# NeoPixelClock.net
KiCad netlist of a schematic drawn in EAGLE
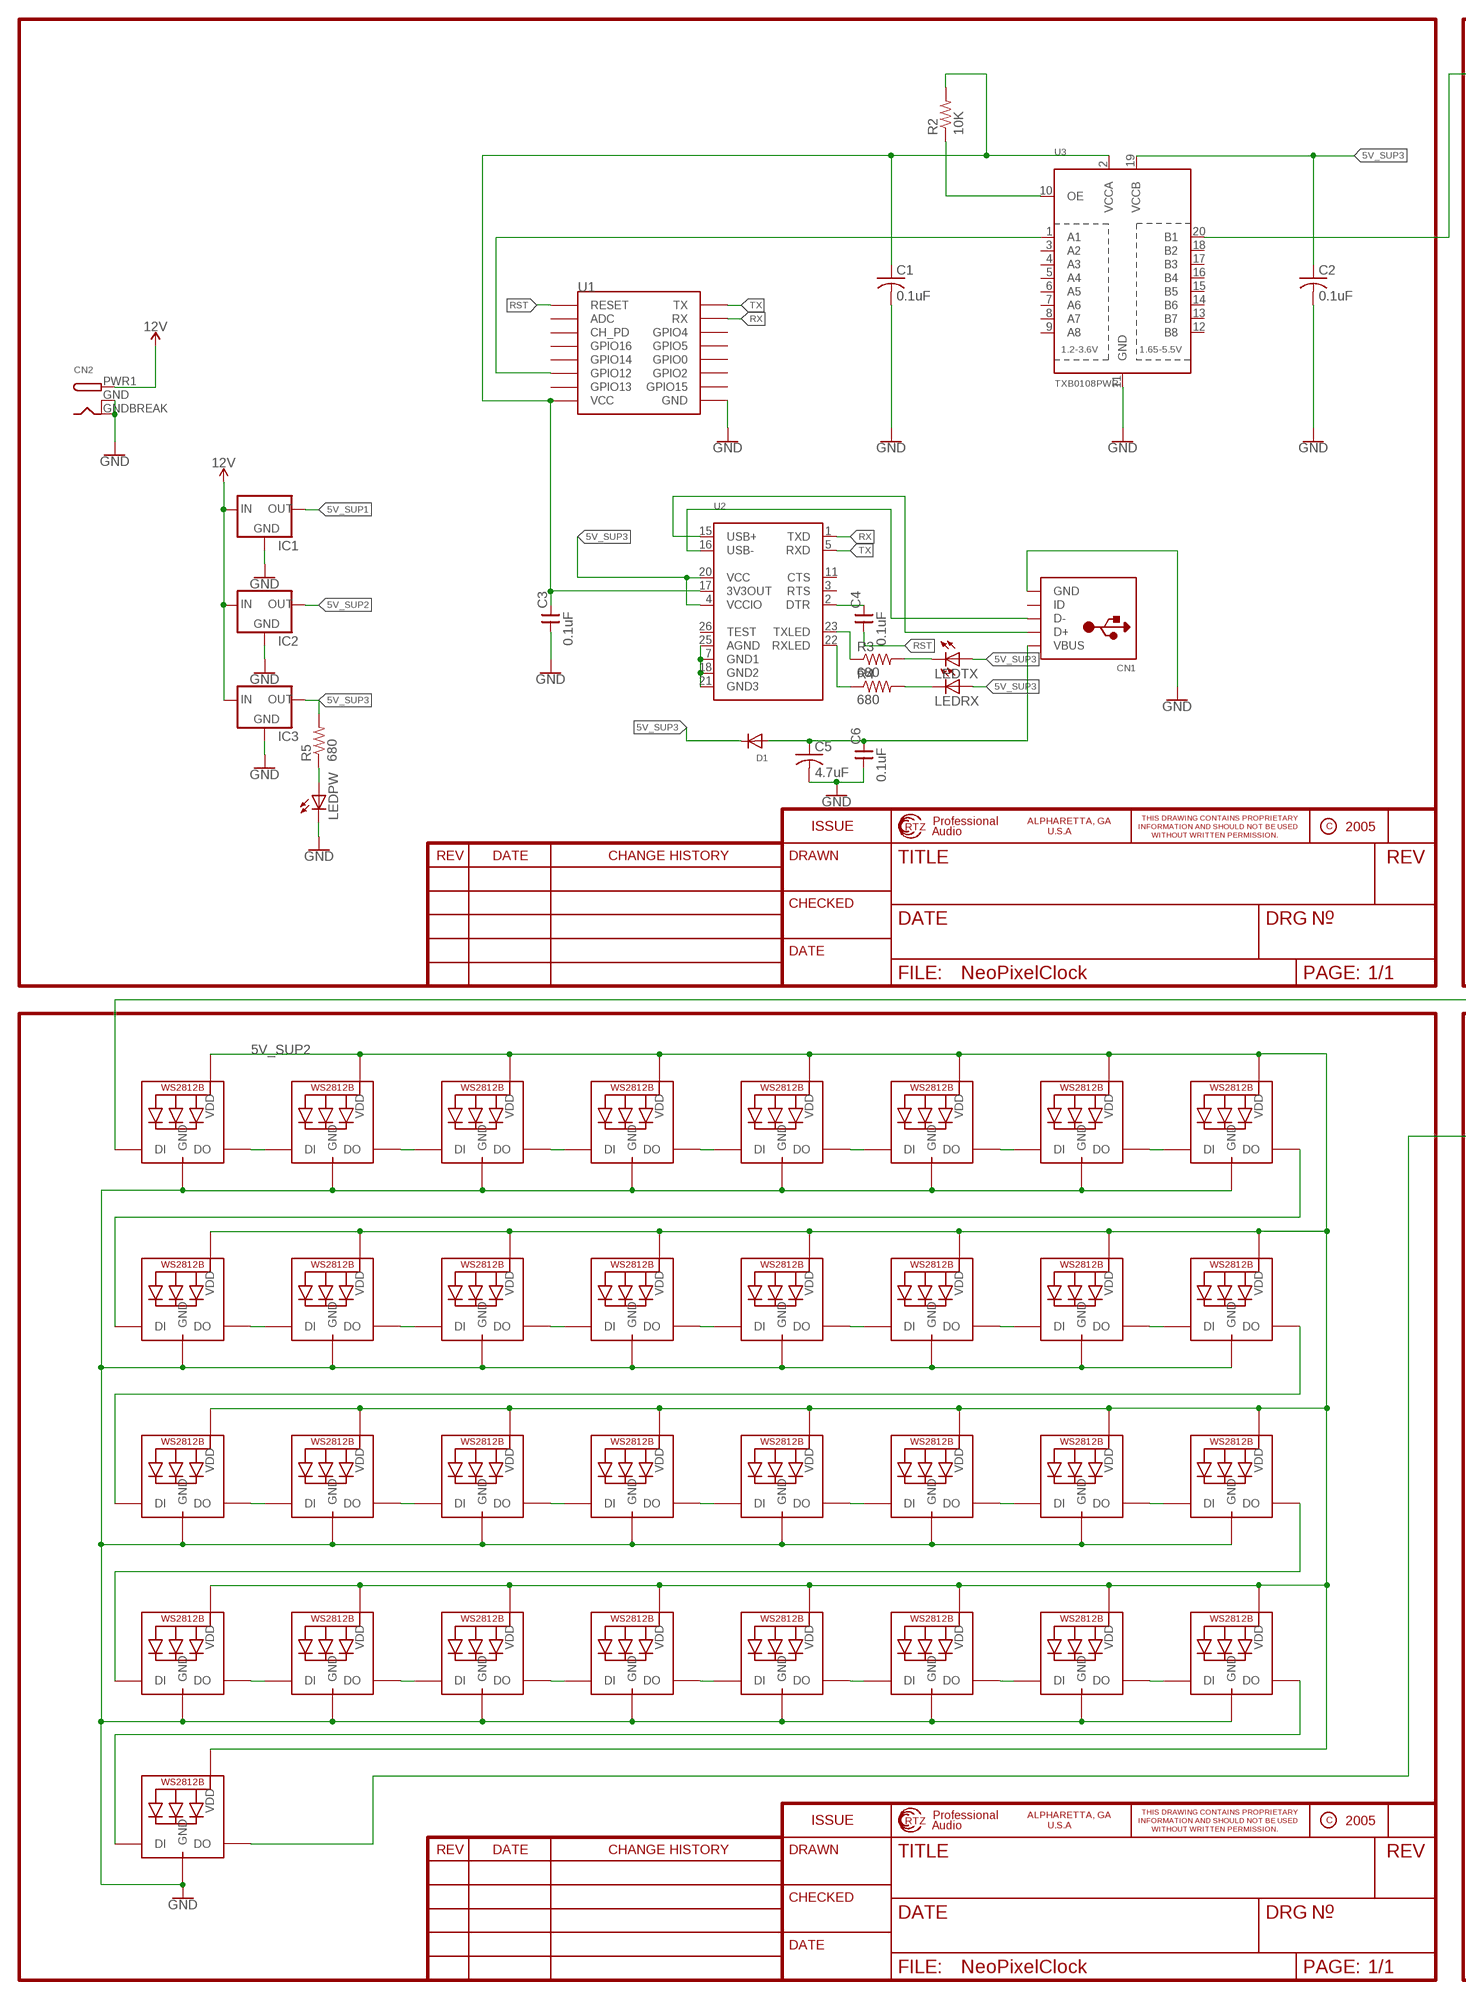
[diagram p0: schematic, sheet 1, part 1 of 2]
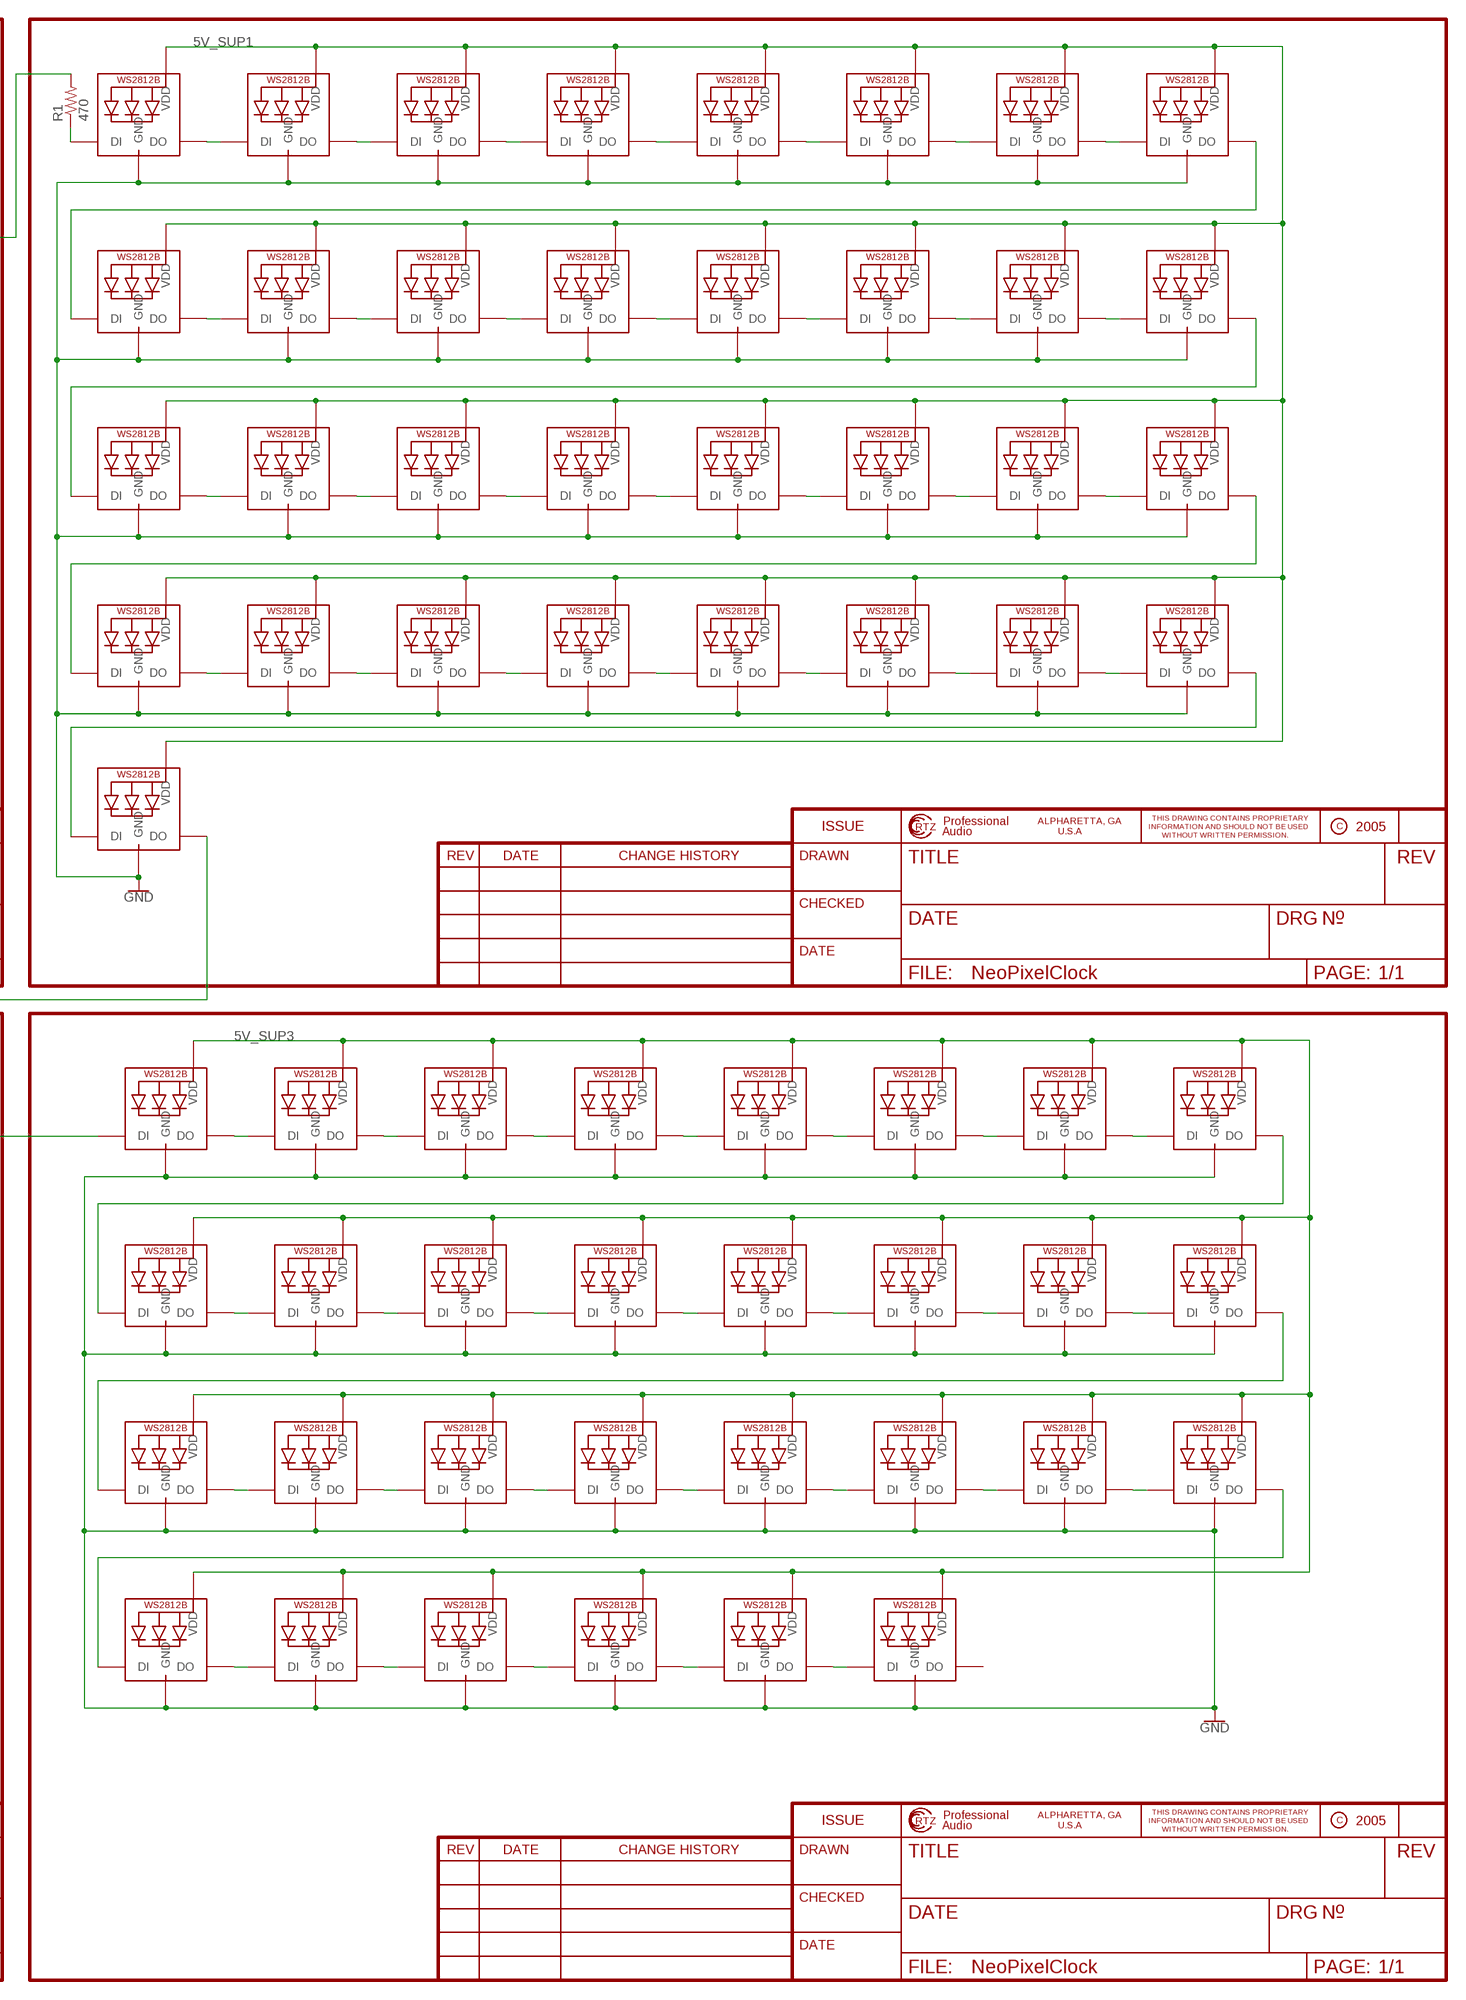
[diagram p1: schematic, sheet 1, part 2 of 2]

(export (version "E")
  (design (tool "Eeschema 10.0.6"))
  (components
    (comp (ref "C1")
      (value "0.1uF")
      (footprint "eagle-import:C0805")
      (libsource (lib "eagle-import") (part "C-USC0805"))
    )
    (comp (ref "C2")
      (value "0.1uF")
      (footprint "eagle-import:C0805")
      (libsource (lib "eagle-import") (part "C-USC0805"))
    )
    (comp (ref "C3")
      (value "0.1uF")
      (footprint "eagle-import:0805")
      (libsource (lib "eagle-import") (part "CNP-0805"))
    )
    (comp (ref "C4")
      (value "0.1uF")
      (footprint "eagle-import:0805")
      (libsource (lib "eagle-import") (part "CNP-0805"))
    )
    (comp (ref "C5")
      (value "4.7uF")
      (footprint "eagle-import:C0805")
      (libsource (lib "eagle-import") (part "C-USC0805"))
    )
    (comp (ref "C6")
      (value "0.1uF")
      (footprint "eagle-import:0805")
      (libsource (lib "eagle-import") (part "CNP-0805"))
    )
    (comp (ref "CN1")
      (value "USBMINIB")
      (footprint "eagle-import:USB-MINIB")
      (libsource (lib "eagle-import") (part "USBMINIB"))
    )
    (comp (ref "CN2")
      (value "DCBARRELSMT")
      (footprint "eagle-import:DCJACK_2MM_SMT")
      (libsource (lib "eagle-import") (part "DCBARRELSMT"))
    )
    (comp (ref "D1")
      (value "DIODESOD-123")
      (footprint "eagle-import:SOD-123")
      (libsource (lib "eagle-import") (part "DIODESOD-123"))
    )
    (comp (ref "IC1")
      (value "V_REG_78XXSIDE")
      (footprint "eagle-import:78XXL")
      (libsource (lib "eagle-import") (part "V_REG_78XXSIDE"))
    )
    (comp (ref "IC2")
      (value "V_REG_78XXSIDE")
      (footprint "eagle-import:78XXL")
      (libsource (lib "eagle-import") (part "V_REG_78XXSIDE"))
    )
    (comp (ref "IC3")
      (value "V_REG_78XXSIDE")
      (footprint "eagle-import:78XXL")
      (libsource (lib "eagle-import") (part "V_REG_78XXSIDE"))
    )
    (comp (ref "LED1")
      (value "WS2812B5050")
      (footprint "eagle-import:WS2812B")
      (libsource (lib "eagle-import") (part "WS2812B5050"))
    )
    (comp (ref "LED2")
      (value "WS2812B5050")
      (footprint "eagle-import:WS2812B")
      (libsource (lib "eagle-import") (part "WS2812B5050"))
    )
    (comp (ref "LED3")
      (value "WS2812B5050")
      (footprint "eagle-import:WS2812B")
      (libsource (lib "eagle-import") (part "WS2812B5050"))
    )
    (comp (ref "LED4")
      (value "WS2812B5050")
      (footprint "eagle-import:WS2812B")
      (libsource (lib "eagle-import") (part "WS2812B5050"))
    )
    (comp (ref "LED5")
      (value "WS2812B5050")
      (footprint "eagle-import:WS2812B")
      (libsource (lib "eagle-import") (part "WS2812B5050"))
    )
    (comp (ref "LED6")
      (value "WS2812B5050")
      (footprint "eagle-import:WS2812B")
      (libsource (lib "eagle-import") (part "WS2812B5050"))
    )
    (comp (ref "LED7")
      (value "WS2812B5050")
      (footprint "eagle-import:WS2812B")
      (libsource (lib "eagle-import") (part "WS2812B5050"))
    )
    (comp (ref "LED8")
      (value "WS2812B5050")
      (footprint "eagle-import:WS2812B")
      (libsource (lib "eagle-import") (part "WS2812B5050"))
    )
    (comp (ref "LED9")
      (value "WS2812B5050")
      (footprint "eagle-import:WS2812B")
      (libsource (lib "eagle-import") (part "WS2812B5050"))
    )
    (comp (ref "LED10")
      (value "WS2812B5050")
      (footprint "eagle-import:WS2812B")
      (libsource (lib "eagle-import") (part "WS2812B5050"))
    )
    (comp (ref "LED11")
      (value "WS2812B5050")
      (footprint "eagle-import:WS2812B")
      (libsource (lib "eagle-import") (part "WS2812B5050"))
    )
    (comp (ref "LED12")
      (value "WS2812B5050")
      (footprint "eagle-import:WS2812B")
      (libsource (lib "eagle-import") (part "WS2812B5050"))
    )
    (comp (ref "LED13")
      (value "WS2812B5050")
      (footprint "eagle-import:WS2812B")
      (libsource (lib "eagle-import") (part "WS2812B5050"))
    )
    (comp (ref "LED14")
      (value "WS2812B5050")
      (footprint "eagle-import:WS2812B")
      (libsource (lib "eagle-import") (part "WS2812B5050"))
    )
    (comp (ref "LED15")
      (value "WS2812B5050")
      (footprint "eagle-import:WS2812B")
      (libsource (lib "eagle-import") (part "WS2812B5050"))
    )
    (comp (ref "LED16")
      (value "WS2812B5050")
      (footprint "eagle-import:WS2812B")
      (libsource (lib "eagle-import") (part "WS2812B5050"))
    )
    (comp (ref "LED17")
      (value "WS2812B5050")
      (footprint "eagle-import:WS2812B")
      (libsource (lib "eagle-import") (part "WS2812B5050"))
    )
    (comp (ref "LED18")
      (value "WS2812B5050")
      (footprint "eagle-import:WS2812B")
      (libsource (lib "eagle-import") (part "WS2812B5050"))
    )
    (comp (ref "LED19")
      (value "WS2812B5050")
      (footprint "eagle-import:WS2812B")
      (libsource (lib "eagle-import") (part "WS2812B5050"))
    )
    (comp (ref "LED20")
      (value "WS2812B5050")
      (footprint "eagle-import:WS2812B")
      (libsource (lib "eagle-import") (part "WS2812B5050"))
    )
    (comp (ref "LED21")
      (value "WS2812B5050")
      (footprint "eagle-import:WS2812B")
      (libsource (lib "eagle-import") (part "WS2812B5050"))
    )
    (comp (ref "LED22")
      (value "WS2812B5050")
      (footprint "eagle-import:WS2812B")
      (libsource (lib "eagle-import") (part "WS2812B5050"))
    )
    (comp (ref "LED23")
      (value "WS2812B5050")
      (footprint "eagle-import:WS2812B")
      (libsource (lib "eagle-import") (part "WS2812B5050"))
    )
    (comp (ref "LED24")
      (value "WS2812B5050")
      (footprint "eagle-import:WS2812B")
      (libsource (lib "eagle-import") (part "WS2812B5050"))
    )
    (comp (ref "LED25")
      (value "WS2812B5050")
      (footprint "eagle-import:WS2812B")
      (libsource (lib "eagle-import") (part "WS2812B5050"))
    )
    (comp (ref "LED26")
      (value "WS2812B5050")
      (footprint "eagle-import:WS2812B")
      (libsource (lib "eagle-import") (part "WS2812B5050"))
    )
    (comp (ref "LED27")
      (value "WS2812B5050")
      (footprint "eagle-import:WS2812B")
      (libsource (lib "eagle-import") (part "WS2812B5050"))
    )
    (comp (ref "LED28")
      (value "WS2812B5050")
      (footprint "eagle-import:WS2812B")
      (libsource (lib "eagle-import") (part "WS2812B5050"))
    )
    (comp (ref "LED29")
      (value "WS2812B5050")
      (footprint "eagle-import:WS2812B")
      (libsource (lib "eagle-import") (part "WS2812B5050"))
    )
    (comp (ref "LED30")
      (value "WS2812B5050")
      (footprint "eagle-import:WS2812B")
      (libsource (lib "eagle-import") (part "WS2812B5050"))
    )
    (comp (ref "LED31")
      (value "WS2812B5050")
      (footprint "eagle-import:WS2812B")
      (libsource (lib "eagle-import") (part "WS2812B5050"))
    )
    (comp (ref "LED32")
      (value "WS2812B5050")
      (footprint "eagle-import:WS2812B")
      (libsource (lib "eagle-import") (part "WS2812B5050"))
    )
    (comp (ref "LED33")
      (value "WS2812B5050")
      (footprint "eagle-import:WS2812B")
      (libsource (lib "eagle-import") (part "WS2812B5050"))
    )
    (comp (ref "LED34")
      (value "WS2812B5050")
      (footprint "eagle-import:WS2812B")
      (libsource (lib "eagle-import") (part "WS2812B5050"))
    )
    (comp (ref "LED35")
      (value "WS2812B5050")
      (footprint "eagle-import:WS2812B")
      (libsource (lib "eagle-import") (part "WS2812B5050"))
    )
    (comp (ref "LED36")
      (value "WS2812B5050")
      (footprint "eagle-import:WS2812B")
      (libsource (lib "eagle-import") (part "WS2812B5050"))
    )
    (comp (ref "LED37")
      (value "WS2812B5050")
      (footprint "eagle-import:WS2812B")
      (libsource (lib "eagle-import") (part "WS2812B5050"))
    )
    (comp (ref "LED38")
      (value "WS2812B5050")
      (footprint "eagle-import:WS2812B")
      (libsource (lib "eagle-import") (part "WS2812B5050"))
    )
    (comp (ref "LED39")
      (value "WS2812B5050")
      (footprint "eagle-import:WS2812B")
      (libsource (lib "eagle-import") (part "WS2812B5050"))
    )
    (comp (ref "LED40")
      (value "WS2812B5050")
      (footprint "eagle-import:WS2812B")
      (libsource (lib "eagle-import") (part "WS2812B5050"))
    )
    (comp (ref "LED41")
      (value "WS2812B5050")
      (footprint "eagle-import:WS2812B")
      (libsource (lib "eagle-import") (part "WS2812B5050"))
    )
    (comp (ref "LED42")
      (value "WS2812B5050")
      (footprint "eagle-import:WS2812B")
      (libsource (lib "eagle-import") (part "WS2812B5050"))
    )
    (comp (ref "LED43")
      (value "WS2812B5050")
      (footprint "eagle-import:WS2812B")
      (libsource (lib "eagle-import") (part "WS2812B5050"))
    )
    (comp (ref "LED44")
      (value "WS2812B5050")
      (footprint "eagle-import:WS2812B")
      (libsource (lib "eagle-import") (part "WS2812B5050"))
    )
    (comp (ref "LED45")
      (value "WS2812B5050")
      (footprint "eagle-import:WS2812B")
      (libsource (lib "eagle-import") (part "WS2812B5050"))
    )
    (comp (ref "LED46")
      (value "WS2812B5050")
      (footprint "eagle-import:WS2812B")
      (libsource (lib "eagle-import") (part "WS2812B5050"))
    )
    (comp (ref "LED47")
      (value "WS2812B5050")
      (footprint "eagle-import:WS2812B")
      (libsource (lib "eagle-import") (part "WS2812B5050"))
    )
    (comp (ref "LED48")
      (value "WS2812B5050")
      (footprint "eagle-import:WS2812B")
      (libsource (lib "eagle-import") (part "WS2812B5050"))
    )
    (comp (ref "LED49")
      (value "WS2812B5050")
      (footprint "eagle-import:WS2812B")
      (libsource (lib "eagle-import") (part "WS2812B5050"))
    )
    (comp (ref "LED50")
      (value "WS2812B5050")
      (footprint "eagle-import:WS2812B")
      (libsource (lib "eagle-import") (part "WS2812B5050"))
    )
    (comp (ref "LED51")
      (value "WS2812B5050")
      (footprint "eagle-import:WS2812B")
      (libsource (lib "eagle-import") (part "WS2812B5050"))
    )
    (comp (ref "LED52")
      (value "WS2812B5050")
      (footprint "eagle-import:WS2812B")
      (libsource (lib "eagle-import") (part "WS2812B5050"))
    )
    (comp (ref "LED53")
      (value "WS2812B5050")
      (footprint "eagle-import:WS2812B")
      (libsource (lib "eagle-import") (part "WS2812B5050"))
    )
    (comp (ref "LED54")
      (value "WS2812B5050")
      (footprint "eagle-import:WS2812B")
      (libsource (lib "eagle-import") (part "WS2812B5050"))
    )
    (comp (ref "LED55")
      (value "WS2812B5050")
      (footprint "eagle-import:WS2812B")
      (libsource (lib "eagle-import") (part "WS2812B5050"))
    )
    (comp (ref "LED56")
      (value "WS2812B5050")
      (footprint "eagle-import:WS2812B")
      (libsource (lib "eagle-import") (part "WS2812B5050"))
    )
    (comp (ref "LED57")
      (value "WS2812B5050")
      (footprint "eagle-import:WS2812B")
      (libsource (lib "eagle-import") (part "WS2812B5050"))
    )
    (comp (ref "LED58")
      (value "WS2812B5050")
      (footprint "eagle-import:WS2812B")
      (libsource (lib "eagle-import") (part "WS2812B5050"))
    )
    (comp (ref "LED59")
      (value "WS2812B5050")
      (footprint "eagle-import:WS2812B")
      (libsource (lib "eagle-import") (part "WS2812B5050"))
    )
    (comp (ref "LED60")
      (value "WS2812B5050")
      (footprint "eagle-import:WS2812B")
      (libsource (lib "eagle-import") (part "WS2812B5050"))
    )
    (comp (ref "LED61")
      (value "WS2812B5050")
      (footprint "eagle-import:WS2812B")
      (libsource (lib "eagle-import") (part "WS2812B5050"))
    )
    (comp (ref "LED62")
      (value "WS2812B5050")
      (footprint "eagle-import:WS2812B")
      (libsource (lib "eagle-import") (part "WS2812B5050"))
    )
    (comp (ref "LED63")
      (value "WS2812B5050")
      (footprint "eagle-import:WS2812B")
      (libsource (lib "eagle-import") (part "WS2812B5050"))
    )
    (comp (ref "LED64")
      (value "WS2812B5050")
      (footprint "eagle-import:WS2812B")
      (libsource (lib "eagle-import") (part "WS2812B5050"))
    )
    (comp (ref "LED65")
      (value "WS2812B5050")
      (footprint "eagle-import:WS2812B")
      (libsource (lib "eagle-import") (part "WS2812B5050"))
    )
    (comp (ref "LED66")
      (value "WS2812B5050")
      (footprint "eagle-import:WS2812B")
      (libsource (lib "eagle-import") (part "WS2812B5050"))
    )
    (comp (ref "LED67")
      (value "WS2812B5050")
      (footprint "eagle-import:WS2812B")
      (libsource (lib "eagle-import") (part "WS2812B5050"))
    )
    (comp (ref "LED68")
      (value "WS2812B5050")
      (footprint "eagle-import:WS2812B")
      (libsource (lib "eagle-import") (part "WS2812B5050"))
    )
    (comp (ref "LED69")
      (value "WS2812B5050")
      (footprint "eagle-import:WS2812B")
      (libsource (lib "eagle-import") (part "WS2812B5050"))
    )
    (comp (ref "LED70")
      (value "WS2812B5050")
      (footprint "eagle-import:WS2812B")
      (libsource (lib "eagle-import") (part "WS2812B5050"))
    )
    (comp (ref "LED71")
      (value "WS2812B5050")
      (footprint "eagle-import:WS2812B")
      (libsource (lib "eagle-import") (part "WS2812B5050"))
    )
    (comp (ref "LED72")
      (value "WS2812B5050")
      (footprint "eagle-import:WS2812B")
      (libsource (lib "eagle-import") (part "WS2812B5050"))
    )
    (comp (ref "LED73")
      (value "WS2812B5050")
      (footprint "eagle-import:WS2812B")
      (libsource (lib "eagle-import") (part "WS2812B5050"))
    )
    (comp (ref "LED74")
      (value "WS2812B5050")
      (footprint "eagle-import:WS2812B")
      (libsource (lib "eagle-import") (part "WS2812B5050"))
    )
    (comp (ref "LED75")
      (value "WS2812B5050")
      (footprint "eagle-import:WS2812B")
      (libsource (lib "eagle-import") (part "WS2812B5050"))
    )
    (comp (ref "LED76")
      (value "WS2812B5050")
      (footprint "eagle-import:WS2812B")
      (libsource (lib "eagle-import") (part "WS2812B5050"))
    )
    (comp (ref "LED77")
      (value "WS2812B5050")
      (footprint "eagle-import:WS2812B")
      (libsource (lib "eagle-import") (part "WS2812B5050"))
    )
    (comp (ref "LED78")
      (value "WS2812B5050")
      (footprint "eagle-import:WS2812B")
      (libsource (lib "eagle-import") (part "WS2812B5050"))
    )
    (comp (ref "LED79")
      (value "WS2812B5050")
      (footprint "eagle-import:WS2812B")
      (libsource (lib "eagle-import") (part "WS2812B5050"))
    )
    (comp (ref "LED80")
      (value "WS2812B5050")
      (footprint "eagle-import:WS2812B")
      (libsource (lib "eagle-import") (part "WS2812B5050"))
    )
    (comp (ref "LED81")
      (value "WS2812B5050")
      (footprint "eagle-import:WS2812B")
      (libsource (lib "eagle-import") (part "WS2812B5050"))
    )
    (comp (ref "LED82")
      (value "WS2812B5050")
      (footprint "eagle-import:WS2812B")
      (libsource (lib "eagle-import") (part "WS2812B5050"))
    )
    (comp (ref "LED83")
      (value "WS2812B5050")
      (footprint "eagle-import:WS2812B")
      (libsource (lib "eagle-import") (part "WS2812B5050"))
    )
    (comp (ref "LED84")
      (value "WS2812B5050")
      (footprint "eagle-import:WS2812B")
      (libsource (lib "eagle-import") (part "WS2812B5050"))
    )
    (comp (ref "LED85")
      (value "WS2812B5050")
      (footprint "eagle-import:WS2812B")
      (libsource (lib "eagle-import") (part "WS2812B5050"))
    )
    (comp (ref "LED86")
      (value "WS2812B5050")
      (footprint "eagle-import:WS2812B")
      (libsource (lib "eagle-import") (part "WS2812B5050"))
    )
    (comp (ref "LED87")
      (value "WS2812B5050")
      (footprint "eagle-import:WS2812B")
      (libsource (lib "eagle-import") (part "WS2812B5050"))
    )
    (comp (ref "LED88")
      (value "WS2812B5050")
      (footprint "eagle-import:WS2812B")
      (libsource (lib "eagle-import") (part "WS2812B5050"))
    )
    (comp (ref "LED89")
      (value "WS2812B5050")
      (footprint "eagle-import:WS2812B")
      (libsource (lib "eagle-import") (part "WS2812B5050"))
    )
    (comp (ref "LED90")
      (value "WS2812B5050")
      (footprint "eagle-import:WS2812B")
      (libsource (lib "eagle-import") (part "WS2812B5050"))
    )
    (comp (ref "LED91")
      (value "WS2812B5050")
      (footprint "eagle-import:WS2812B")
      (libsource (lib "eagle-import") (part "WS2812B5050"))
    )
    (comp (ref "LED92")
      (value "WS2812B5050")
      (footprint "eagle-import:WS2812B")
      (libsource (lib "eagle-import") (part "WS2812B5050"))
    )
    (comp (ref "LED93")
      (value "WS2812B5050")
      (footprint "eagle-import:WS2812B")
      (libsource (lib "eagle-import") (part "WS2812B5050"))
    )
    (comp (ref "LED94")
      (value "WS2812B5050")
      (footprint "eagle-import:WS2812B")
      (libsource (lib "eagle-import") (part "WS2812B5050"))
    )
    (comp (ref "LED95")
      (value "WS2812B5050")
      (footprint "eagle-import:WS2812B")
      (libsource (lib "eagle-import") (part "WS2812B5050"))
    )
    (comp (ref "LED96")
      (value "WS2812B5050")
      (footprint "eagle-import:WS2812B")
      (libsource (lib "eagle-import") (part "WS2812B5050"))
    )
    (comp (ref "LEDPW")
      (value "LEDCHIP-LED0805")
      (footprint "eagle-import:CHIP-LED0805")
      (libsource (lib "eagle-import") (part "LEDCHIP-LED0805"))
    )
    (comp (ref "LEDRX")
      (value "LEDCHIP-LED0805")
      (footprint "eagle-import:CHIP-LED0805")
      (libsource (lib "eagle-import") (part "LEDCHIP-LED0805"))
    )
    (comp (ref "LEDTX")
      (value "LEDCHIP-LED0805")
      (footprint "eagle-import:CHIP-LED0805")
      (libsource (lib "eagle-import") (part "LEDCHIP-LED0805"))
    )
    (comp (ref "R1")
      (value "470")
      (footprint "eagle-import:M0805")
      (libsource (lib "eagle-import") (part "adafruit_420_R-US_M0805"))
    )
    (comp (ref "R2")
      (value "10K")
      (footprint "eagle-import:R0805")
      (libsource (lib "eagle-import") (part "R-US_R0805"))
    )
    (comp (ref "R3")
      (value "680")
      (footprint "eagle-import:R0805")
      (libsource (lib "eagle-import") (part "adafruit_420_R-US_R0805"))
    )
    (comp (ref "R4")
      (value "680")
      (footprint "eagle-import:R0805")
      (libsource (lib "eagle-import") (part "adafruit_420_R-US_R0805"))
    )
    (comp (ref "R5")
      (value "680")
      (footprint "eagle-import:R0805")
      (libsource (lib "eagle-import") (part "adafruit_420_R-US_R0805"))
    )
    (comp (ref "U1")
      (value "ESP12")
      (footprint "eagle-import:ESP12")
      (libsource (lib "eagle-import") (part "ESP12"))
    )
    (comp (ref "U2")
      (value "FT232RLSSOP28")
      (footprint "eagle-import:SSOP28DB")
      (libsource (lib "eagle-import") (part "FT232RLSSOP28"))
    )
    (comp (ref "U3")
      (value "TXB0108PWR")
      (footprint "eagle-import:TSSOP20")
      (libsource (lib "eagle-import") (part "TXB0108PWR"))
    )
  )
  (nets
    (net (code "1") (name "5V_SUP1") (class "Default")
      (node (ref "IC1") (pin "OUT") (pinfunction "OUT_OUT") (pintype "output"))
      (node (ref "LED1") (pin "1-VDD") (pinfunction "VDD_1-VDD") (pintype "power_in"))
      (node (ref "LED10") (pin "1-VDD") (pinfunction "VDD_1-VDD") (pintype "power_in"))
      (node (ref "LED11") (pin "1-VDD") (pinfunction "VDD_1-VDD") (pintype "power_in"))
      (node (ref "LED12") (pin "1-VDD") (pinfunction "VDD_1-VDD") (pintype "power_in"))
      (node (ref "LED13") (pin "1-VDD") (pinfunction "VDD_1-VDD") (pintype "power_in"))
      (node (ref "LED14") (pin "1-VDD") (pinfunction "VDD_1-VDD") (pintype "power_in"))
      (node (ref "LED15") (pin "1-VDD") (pinfunction "VDD_1-VDD") (pintype "power_in"))
      (node (ref "LED16") (pin "1-VDD") (pinfunction "VDD_1-VDD") (pintype "power_in"))
      (node (ref "LED17") (pin "1-VDD") (pinfunction "VDD_1-VDD") (pintype "power_in"))
      (node (ref "LED18") (pin "1-VDD") (pinfunction "VDD_1-VDD") (pintype "power_in"))
      (node (ref "LED19") (pin "1-VDD") (pinfunction "VDD_1-VDD") (pintype "power_in"))
      (node (ref "LED2") (pin "1-VDD") (pinfunction "VDD_1-VDD") (pintype "power_in"))
      (node (ref "LED20") (pin "1-VDD") (pinfunction "VDD_1-VDD") (pintype "power_in"))
      (node (ref "LED21") (pin "1-VDD") (pinfunction "VDD_1-VDD") (pintype "power_in"))
      (node (ref "LED22") (pin "1-VDD") (pinfunction "VDD_1-VDD") (pintype "power_in"))
      (node (ref "LED23") (pin "1-VDD") (pinfunction "VDD_1-VDD") (pintype "power_in"))
      (node (ref "LED24") (pin "1-VDD") (pinfunction "VDD_1-VDD") (pintype "power_in"))
      (node (ref "LED25") (pin "1-VDD") (pinfunction "VDD_1-VDD") (pintype "power_in"))
      (node (ref "LED26") (pin "1-VDD") (pinfunction "VDD_1-VDD") (pintype "power_in"))
      (node (ref "LED27") (pin "1-VDD") (pinfunction "VDD_1-VDD") (pintype "power_in"))
      (node (ref "LED28") (pin "1-VDD") (pinfunction "VDD_1-VDD") (pintype "power_in"))
      (node (ref "LED29") (pin "1-VDD") (pinfunction "VDD_1-VDD") (pintype "power_in"))
      (node (ref "LED3") (pin "1-VDD") (pinfunction "VDD_1-VDD") (pintype "power_in"))
      (node (ref "LED30") (pin "1-VDD") (pinfunction "VDD_1-VDD") (pintype "power_in"))
      (node (ref "LED31") (pin "1-VDD") (pinfunction "VDD_1-VDD") (pintype "power_in"))
      (node (ref "LED32") (pin "1-VDD") (pinfunction "VDD_1-VDD") (pintype "power_in"))
      (node (ref "LED33") (pin "1-VDD") (pinfunction "VDD_1-VDD") (pintype "power_in"))
      (node (ref "LED4") (pin "1-VDD") (pinfunction "VDD_1-VDD") (pintype "power_in"))
      (node (ref "LED5") (pin "1-VDD") (pinfunction "VDD_1-VDD") (pintype "power_in"))
      (node (ref "LED6") (pin "1-VDD") (pinfunction "VDD_1-VDD") (pintype "power_in"))
      (node (ref "LED7") (pin "1-VDD") (pinfunction "VDD_1-VDD") (pintype "power_in"))
      (node (ref "LED8") (pin "1-VDD") (pinfunction "VDD_1-VDD") (pintype "power_in"))
      (node (ref "LED9") (pin "1-VDD") (pinfunction "VDD_1-VDD") (pintype "power_in"))
    )
    (net (code "2") (name "5V_SUP2") (class "Default")
      (node (ref "IC2") (pin "OUT") (pinfunction "OUT_OUT") (pintype "output"))
      (node (ref "LED34") (pin "1-VDD") (pinfunction "VDD_1-VDD") (pintype "power_in"))
      (node (ref "LED35") (pin "1-VDD") (pinfunction "VDD_1-VDD") (pintype "power_in"))
      (node (ref "LED36") (pin "1-VDD") (pinfunction "VDD_1-VDD") (pintype "power_in"))
      (node (ref "LED37") (pin "1-VDD") (pinfunction "VDD_1-VDD") (pintype "power_in"))
      (node (ref "LED38") (pin "1-VDD") (pinfunction "VDD_1-VDD") (pintype "power_in"))
      (node (ref "LED39") (pin "1-VDD") (pinfunction "VDD_1-VDD") (pintype "power_in"))
      (node (ref "LED40") (pin "1-VDD") (pinfunction "VDD_1-VDD") (pintype "power_in"))
      (node (ref "LED41") (pin "1-VDD") (pinfunction "VDD_1-VDD") (pintype "power_in"))
      (node (ref "LED42") (pin "1-VDD") (pinfunction "VDD_1-VDD") (pintype "power_in"))
      (node (ref "LED43") (pin "1-VDD") (pinfunction "VDD_1-VDD") (pintype "power_in"))
      (node (ref "LED44") (pin "1-VDD") (pinfunction "VDD_1-VDD") (pintype "power_in"))
      (node (ref "LED45") (pin "1-VDD") (pinfunction "VDD_1-VDD") (pintype "power_in"))
      (node (ref "LED46") (pin "1-VDD") (pinfunction "VDD_1-VDD") (pintype "power_in"))
      (node (ref "LED47") (pin "1-VDD") (pinfunction "VDD_1-VDD") (pintype "power_in"))
      (node (ref "LED48") (pin "1-VDD") (pinfunction "VDD_1-VDD") (pintype "power_in"))
      (node (ref "LED49") (pin "1-VDD") (pinfunction "VDD_1-VDD") (pintype "power_in"))
      (node (ref "LED50") (pin "1-VDD") (pinfunction "VDD_1-VDD") (pintype "power_in"))
      (node (ref "LED51") (pin "1-VDD") (pinfunction "VDD_1-VDD") (pintype "power_in"))
      (node (ref "LED52") (pin "1-VDD") (pinfunction "VDD_1-VDD") (pintype "power_in"))
      (node (ref "LED53") (pin "1-VDD") (pinfunction "VDD_1-VDD") (pintype "power_in"))
      (node (ref "LED54") (pin "1-VDD") (pinfunction "VDD_1-VDD") (pintype "power_in"))
      (node (ref "LED55") (pin "1-VDD") (pinfunction "VDD_1-VDD") (pintype "power_in"))
      (node (ref "LED56") (pin "1-VDD") (pinfunction "VDD_1-VDD") (pintype "power_in"))
      (node (ref "LED57") (pin "1-VDD") (pinfunction "VDD_1-VDD") (pintype "power_in"))
      (node (ref "LED58") (pin "1-VDD") (pinfunction "VDD_1-VDD") (pintype "power_in"))
      (node (ref "LED59") (pin "1-VDD") (pinfunction "VDD_1-VDD") (pintype "power_in"))
      (node (ref "LED60") (pin "1-VDD") (pinfunction "VDD_1-VDD") (pintype "power_in"))
      (node (ref "LED61") (pin "1-VDD") (pinfunction "VDD_1-VDD") (pintype "power_in"))
      (node (ref "LED62") (pin "1-VDD") (pinfunction "VDD_1-VDD") (pintype "power_in"))
      (node (ref "LED63") (pin "1-VDD") (pinfunction "VDD_1-VDD") (pintype "power_in"))
      (node (ref "LED64") (pin "1-VDD") (pinfunction "VDD_1-VDD") (pintype "power_in"))
      (node (ref "LED65") (pin "1-VDD") (pinfunction "VDD_1-VDD") (pintype "power_in"))
      (node (ref "LED66") (pin "1-VDD") (pinfunction "VDD_1-VDD") (pintype "power_in"))
    )
    (net (code "3") (name "5V_SUP3") (class "Default")
      (node (ref "C2") (pin "1") (pinfunction "1_1") (pintype "passive"))
      (node (ref "D1") (pin "C") (pinfunction "C_C") (pintype "passive"))
      (node (ref "IC3") (pin "OUT") (pinfunction "OUT_OUT") (pintype "output"))
      (node (ref "LED67") (pin "1-VDD") (pinfunction "VDD_1-VDD") (pintype "power_in"))
      (node (ref "LED68") (pin "1-VDD") (pinfunction "VDD_1-VDD") (pintype "power_in"))
      (node (ref "LED69") (pin "1-VDD") (pinfunction "VDD_1-VDD") (pintype "power_in"))
      (node (ref "LED70") (pin "1-VDD") (pinfunction "VDD_1-VDD") (pintype "power_in"))
      (node (ref "LED71") (pin "1-VDD") (pinfunction "VDD_1-VDD") (pintype "power_in"))
      (node (ref "LED72") (pin "1-VDD") (pinfunction "VDD_1-VDD") (pintype "power_in"))
      (node (ref "LED73") (pin "1-VDD") (pinfunction "VDD_1-VDD") (pintype "power_in"))
      (node (ref "LED74") (pin "1-VDD") (pinfunction "VDD_1-VDD") (pintype "power_in"))
      (node (ref "LED75") (pin "1-VDD") (pinfunction "VDD_1-VDD") (pintype "power_in"))
      (node (ref "LED76") (pin "1-VDD") (pinfunction "VDD_1-VDD") (pintype "power_in"))
      (node (ref "LED77") (pin "1-VDD") (pinfunction "VDD_1-VDD") (pintype "power_in"))
      (node (ref "LED78") (pin "1-VDD") (pinfunction "VDD_1-VDD") (pintype "power_in"))
      (node (ref "LED79") (pin "1-VDD") (pinfunction "VDD_1-VDD") (pintype "power_in"))
      (node (ref "LED80") (pin "1-VDD") (pinfunction "VDD_1-VDD") (pintype "power_in"))
      (node (ref "LED81") (pin "1-VDD") (pinfunction "VDD_1-VDD") (pintype "power_in"))
      (node (ref "LED82") (pin "1-VDD") (pinfunction "VDD_1-VDD") (pintype "power_in"))
      (node (ref "LED83") (pin "1-VDD") (pinfunction "VDD_1-VDD") (pintype "power_in"))
      (node (ref "LED84") (pin "1-VDD") (pinfunction "VDD_1-VDD") (pintype "power_in"))
      (node (ref "LED85") (pin "1-VDD") (pinfunction "VDD_1-VDD") (pintype "power_in"))
      (node (ref "LED86") (pin "1-VDD") (pinfunction "VDD_1-VDD") (pintype "power_in"))
      (node (ref "LED87") (pin "1-VDD") (pinfunction "VDD_1-VDD") (pintype "power_in"))
      (node (ref "LED88") (pin "1-VDD") (pinfunction "VDD_1-VDD") (pintype "power_in"))
      (node (ref "LED89") (pin "1-VDD") (pinfunction "VDD_1-VDD") (pintype "power_in"))
      (node (ref "LED90") (pin "1-VDD") (pinfunction "VDD_1-VDD") (pintype "power_in"))
      (node (ref "LED91") (pin "1-VDD") (pinfunction "VDD_1-VDD") (pintype "power_in"))
      (node (ref "LED92") (pin "1-VDD") (pinfunction "VDD_1-VDD") (pintype "power_in"))
      (node (ref "LED93") (pin "1-VDD") (pinfunction "VDD_1-VDD") (pintype "power_in"))
      (node (ref "LED94") (pin "1-VDD") (pinfunction "VDD_1-VDD") (pintype "power_in"))
      (node (ref "LED95") (pin "1-VDD") (pinfunction "VDD_1-VDD") (pintype "power_in"))
      (node (ref "LED96") (pin "1-VDD") (pinfunction "VDD_1-VDD") (pintype "power_in"))
      (node (ref "LEDRX") (pin "A") (pinfunction "A_A") (pintype "passive"))
      (node (ref "LEDTX") (pin "A") (pinfunction "A_A") (pintype "passive"))
      (node (ref "R5") (pin "2") (pinfunction "2_2") (pintype "passive"))
      (node (ref "U2") (pin "20") (pinfunction "VCC_20") (pintype "power_in"))
      (node (ref "U2") (pin "4") (pinfunction "VCCIO_4") (pintype "power_in"))
      (node (ref "U3") (pin "19") (pinfunction "VCCB_19") (pintype "bidirectional"))
    )
    (net (code "4") (name "12V") (class "Default")
      (node (ref "CN2") (pin "PWR1") (pinfunction "PWR_PWR1") (pintype "power_in"))
      (node (ref "IC1") (pin "IN") (pinfunction "IN_IN") (pintype "input"))
      (node (ref "IC2") (pin "IN") (pinfunction "IN_IN") (pintype "input"))
      (node (ref "IC3") (pin "IN") (pinfunction "IN_IN") (pintype "input"))
    )
    (net (code "5") (name "GND") (class "Default")
      (node (ref "C1") (pin "2") (pinfunction "2_2") (pintype "passive"))
      (node (ref "C2") (pin "2") (pinfunction "2_2") (pintype "passive"))
      (node (ref "C3") (pin "1") (pinfunction "1_1") (pintype "passive"))
      (node (ref "C5") (pin "2") (pinfunction "2_2") (pintype "passive"))
      (node (ref "C6") (pin "1") (pinfunction "1_1") (pintype "passive"))
      (node (ref "CN1") (pin "GND") (pinfunction "GND_GND") (pintype "power_in"))
      (node (ref "CN2") (pin "GND") (pinfunction "GNDBREAK_GND") (pintype "power_in"))
      (node (ref "CN2") (pin "GNDBREAK") (pinfunction "GND_GNDBREAK") (pintype "power_in"))
      (node (ref "IC1") (pin "GND") (pinfunction "GND_GND") (pintype "input"))
      (node (ref "IC2") (pin "GND") (pinfunction "GND_GND") (pintype "input"))
      (node (ref "IC3") (pin "GND") (pinfunction "GND_GND") (pintype "input"))
      (node (ref "LED1") (pin "3-GND") (pinfunction "GND_3-GND") (pintype "power_in"))
      (node (ref "LED10") (pin "3-GND") (pinfunction "GND_3-GND") (pintype "power_in"))
      (node (ref "LED11") (pin "3-GND") (pinfunction "GND_3-GND") (pintype "power_in"))
      (node (ref "LED12") (pin "3-GND") (pinfunction "GND_3-GND") (pintype "power_in"))
      (node (ref "LED13") (pin "3-GND") (pinfunction "GND_3-GND") (pintype "power_in"))
      (node (ref "LED14") (pin "3-GND") (pinfunction "GND_3-GND") (pintype "power_in"))
      (node (ref "LED15") (pin "3-GND") (pinfunction "GND_3-GND") (pintype "power_in"))
      (node (ref "LED16") (pin "3-GND") (pinfunction "GND_3-GND") (pintype "power_in"))
      (node (ref "LED17") (pin "3-GND") (pinfunction "GND_3-GND") (pintype "power_in"))
      (node (ref "LED18") (pin "3-GND") (pinfunction "GND_3-GND") (pintype "power_in"))
      (node (ref "LED19") (pin "3-GND") (pinfunction "GND_3-GND") (pintype "power_in"))
      (node (ref "LED2") (pin "3-GND") (pinfunction "GND_3-GND") (pintype "power_in"))
      (node (ref "LED20") (pin "3-GND") (pinfunction "GND_3-GND") (pintype "power_in"))
      (node (ref "LED21") (pin "3-GND") (pinfunction "GND_3-GND") (pintype "power_in"))
      (node (ref "LED22") (pin "3-GND") (pinfunction "GND_3-GND") (pintype "power_in"))
      (node (ref "LED23") (pin "3-GND") (pinfunction "GND_3-GND") (pintype "power_in"))
      (node (ref "LED24") (pin "3-GND") (pinfunction "GND_3-GND") (pintype "power_in"))
      (node (ref "LED25") (pin "3-GND") (pinfunction "GND_3-GND") (pintype "power_in"))
      (node (ref "LED26") (pin "3-GND") (pinfunction "GND_3-GND") (pintype "power_in"))
      (node (ref "LED27") (pin "3-GND") (pinfunction "GND_3-GND") (pintype "power_in"))
      (node (ref "LED28") (pin "3-GND") (pinfunction "GND_3-GND") (pintype "power_in"))
      (node (ref "LED29") (pin "3-GND") (pinfunction "GND_3-GND") (pintype "power_in"))
      (node (ref "LED3") (pin "3-GND") (pinfunction "GND_3-GND") (pintype "power_in"))
      (node (ref "LED30") (pin "3-GND") (pinfunction "GND_3-GND") (pintype "power_in"))
      (node (ref "LED31") (pin "3-GND") (pinfunction "GND_3-GND") (pintype "power_in"))
      (node (ref "LED32") (pin "3-GND") (pinfunction "GND_3-GND") (pintype "power_in"))
      (node (ref "LED33") (pin "3-GND") (pinfunction "GND_3-GND") (pintype "power_in"))
      (node (ref "LED34") (pin "3-GND") (pinfunction "GND_3-GND") (pintype "power_in"))
      (node (ref "LED35") (pin "3-GND") (pinfunction "GND_3-GND") (pintype "power_in"))
      (node (ref "LED36") (pin "3-GND") (pinfunction "GND_3-GND") (pintype "power_in"))
      (node (ref "LED37") (pin "3-GND") (pinfunction "GND_3-GND") (pintype "power_in"))
      (node (ref "LED38") (pin "3-GND") (pinfunction "GND_3-GND") (pintype "power_in"))
      (node (ref "LED39") (pin "3-GND") (pinfunction "GND_3-GND") (pintype "power_in"))
      (node (ref "LED4") (pin "3-GND") (pinfunction "GND_3-GND") (pintype "power_in"))
      (node (ref "LED40") (pin "3-GND") (pinfunction "GND_3-GND") (pintype "power_in"))
      (node (ref "LED41") (pin "3-GND") (pinfunction "GND_3-GND") (pintype "power_in"))
      (node (ref "LED42") (pin "3-GND") (pinfunction "GND_3-GND") (pintype "power_in"))
      (node (ref "LED43") (pin "3-GND") (pinfunction "GND_3-GND") (pintype "power_in"))
      (node (ref "LED44") (pin "3-GND") (pinfunction "GND_3-GND") (pintype "power_in"))
      (node (ref "LED45") (pin "3-GND") (pinfunction "GND_3-GND") (pintype "power_in"))
      (node (ref "LED46") (pin "3-GND") (pinfunction "GND_3-GND") (pintype "power_in"))
      (node (ref "LED47") (pin "3-GND") (pinfunction "GND_3-GND") (pintype "power_in"))
      (node (ref "LED48") (pin "3-GND") (pinfunction "GND_3-GND") (pintype "power_in"))
      (node (ref "LED49") (pin "3-GND") (pinfunction "GND_3-GND") (pintype "power_in"))
      (node (ref "LED5") (pin "3-GND") (pinfunction "GND_3-GND") (pintype "power_in"))
      (node (ref "LED50") (pin "3-GND") (pinfunction "GND_3-GND") (pintype "power_in"))
      (node (ref "LED51") (pin "3-GND") (pinfunction "GND_3-GND") (pintype "power_in"))
      (node (ref "LED52") (pin "3-GND") (pinfunction "GND_3-GND") (pintype "power_in"))
      (node (ref "LED53") (pin "3-GND") (pinfunction "GND_3-GND") (pintype "power_in"))
      (node (ref "LED54") (pin "3-GND") (pinfunction "GND_3-GND") (pintype "power_in"))
      (node (ref "LED55") (pin "3-GND") (pinfunction "GND_3-GND") (pintype "power_in"))
      (node (ref "LED56") (pin "3-GND") (pinfunction "GND_3-GND") (pintype "power_in"))
      (node (ref "LED57") (pin "3-GND") (pinfunction "GND_3-GND") (pintype "power_in"))
      (node (ref "LED58") (pin "3-GND") (pinfunction "GND_3-GND") (pintype "power_in"))
      (node (ref "LED59") (pin "3-GND") (pinfunction "GND_3-GND") (pintype "power_in"))
      (node (ref "LED6") (pin "3-GND") (pinfunction "GND_3-GND") (pintype "power_in"))
      (node (ref "LED60") (pin "3-GND") (pinfunction "GND_3-GND") (pintype "power_in"))
      (node (ref "LED61") (pin "3-GND") (pinfunction "GND_3-GND") (pintype "power_in"))
      (node (ref "LED62") (pin "3-GND") (pinfunction "GND_3-GND") (pintype "power_in"))
      (node (ref "LED63") (pin "3-GND") (pinfunction "GND_3-GND") (pintype "power_in"))
      (node (ref "LED64") (pin "3-GND") (pinfunction "GND_3-GND") (pintype "power_in"))
      (node (ref "LED65") (pin "3-GND") (pinfunction "GND_3-GND") (pintype "power_in"))
      (node (ref "LED66") (pin "3-GND") (pinfunction "GND_3-GND") (pintype "power_in"))
      (node (ref "LED67") (pin "3-GND") (pinfunction "GND_3-GND") (pintype "power_in"))
      (node (ref "LED68") (pin "3-GND") (pinfunction "GND_3-GND") (pintype "power_in"))
      (node (ref "LED69") (pin "3-GND") (pinfunction "GND_3-GND") (pintype "power_in"))
      (node (ref "LED7") (pin "3-GND") (pinfunction "GND_3-GND") (pintype "power_in"))
      (node (ref "LED70") (pin "3-GND") (pinfunction "GND_3-GND") (pintype "power_in"))
      (node (ref "LED71") (pin "3-GND") (pinfunction "GND_3-GND") (pintype "power_in"))
      (node (ref "LED72") (pin "3-GND") (pinfunction "GND_3-GND") (pintype "power_in"))
      (node (ref "LED73") (pin "3-GND") (pinfunction "GND_3-GND") (pintype "power_in"))
      (node (ref "LED74") (pin "3-GND") (pinfunction "GND_3-GND") (pintype "power_in"))
      (node (ref "LED75") (pin "3-GND") (pinfunction "GND_3-GND") (pintype "power_in"))
      (node (ref "LED76") (pin "3-GND") (pinfunction "GND_3-GND") (pintype "power_in"))
      (node (ref "LED77") (pin "3-GND") (pinfunction "GND_3-GND") (pintype "power_in"))
      (node (ref "LED78") (pin "3-GND") (pinfunction "GND_3-GND") (pintype "power_in"))
      (node (ref "LED79") (pin "3-GND") (pinfunction "GND_3-GND") (pintype "power_in"))
      (node (ref "LED8") (pin "3-GND") (pinfunction "GND_3-GND") (pintype "power_in"))
      (node (ref "LED80") (pin "3-GND") (pinfunction "GND_3-GND") (pintype "power_in"))
      (node (ref "LED81") (pin "3-GND") (pinfunction "GND_3-GND") (pintype "power_in"))
      (node (ref "LED82") (pin "3-GND") (pinfunction "GND_3-GND") (pintype "power_in"))
      (node (ref "LED83") (pin "3-GND") (pinfunction "GND_3-GND") (pintype "power_in"))
      (node (ref "LED84") (pin "3-GND") (pinfunction "GND_3-GND") (pintype "power_in"))
      (node (ref "LED85") (pin "3-GND") (pinfunction "GND_3-GND") (pintype "power_in"))
      (node (ref "LED86") (pin "3-GND") (pinfunction "GND_3-GND") (pintype "power_in"))
      (node (ref "LED87") (pin "3-GND") (pinfunction "GND_3-GND") (pintype "power_in"))
      (node (ref "LED88") (pin "3-GND") (pinfunction "GND_3-GND") (pintype "power_in"))
      (node (ref "LED89") (pin "3-GND") (pinfunction "GND_3-GND") (pintype "power_in"))
      (node (ref "LED9") (pin "3-GND") (pinfunction "GND_3-GND") (pintype "power_in"))
      (node (ref "LED90") (pin "3-GND") (pinfunction "GND_3-GND") (pintype "power_in"))
      (node (ref "LED91") (pin "3-GND") (pinfunction "GND_3-GND") (pintype "power_in"))
      (node (ref "LED92") (pin "3-GND") (pinfunction "GND_3-GND") (pintype "power_in"))
      (node (ref "LED93") (pin "3-GND") (pinfunction "GND_3-GND") (pintype "power_in"))
      (node (ref "LED94") (pin "3-GND") (pinfunction "GND_3-GND") (pintype "power_in"))
      (node (ref "LED95") (pin "3-GND") (pinfunction "GND_3-GND") (pintype "power_in"))
      (node (ref "LED96") (pin "3-GND") (pinfunction "GND_3-GND") (pintype "power_in"))
      (node (ref "LEDPW") (pin "C") (pinfunction "C_C") (pintype "passive"))
      (node (ref "U1") (pin "GND") (pinfunction "GND_GND") (pintype "bidirectional"))
      (node (ref "U3") (pin "11") (pinfunction "GND_11") (pintype "bidirectional"))
    )
    (net (code "6") (name "Net-(C5-Pad1)") (class "Default")
      (node (ref "C5") (pin "1") (pinfunction "1_1") (pintype "passive"))
      (node (ref "C6") (pin "2") (pinfunction "2_2") (pintype "passive"))
      (node (ref "CN1") (pin "VBUS") (pinfunction "VBUS_VBUS") (pintype "power_in"))
      (node (ref "D1") (pin "A") (pinfunction "A_A") (pintype "passive"))
    )
    (net (code "7") (name "Net-(LED1-DI)") (class "Default")
      (node (ref "LED1") (pin "4-DIN") (pinfunction "DI_4-DIN") (pintype "input"))
      (node (ref "R1") (pin "1") (pinfunction "1_1") (pintype "passive"))
    )
    (net (code "8") (name "Net-(LED1-DO)") (class "Default")
      (node (ref "LED1") (pin "2-DOUT") (pinfunction "DO_2-DOUT") (pintype "output"))
      (node (ref "LED2") (pin "4-DIN") (pinfunction "DI_4-DIN") (pintype "input"))
    )
    (net (code "9") (name "Net-(LED2-DO)") (class "Default")
      (node (ref "LED2") (pin "2-DOUT") (pinfunction "DO_2-DOUT") (pintype "output"))
      (node (ref "LED3") (pin "4-DIN") (pinfunction "DI_4-DIN") (pintype "input"))
    )
    (net (code "10") (name "Net-(LED3-DO)") (class "Default")
      (node (ref "LED3") (pin "2-DOUT") (pinfunction "DO_2-DOUT") (pintype "output"))
      (node (ref "LED4") (pin "4-DIN") (pinfunction "DI_4-DIN") (pintype "input"))
    )
    (net (code "11") (name "Net-(LED4-DO)") (class "Default")
      (node (ref "LED4") (pin "2-DOUT") (pinfunction "DO_2-DOUT") (pintype "output"))
      (node (ref "LED5") (pin "4-DIN") (pinfunction "DI_4-DIN") (pintype "input"))
    )
    (net (code "12") (name "Net-(LED5-DO)") (class "Default")
      (node (ref "LED5") (pin "2-DOUT") (pinfunction "DO_2-DOUT") (pintype "output"))
      (node (ref "LED6") (pin "4-DIN") (pinfunction "DI_4-DIN") (pintype "input"))
    )
    (net (code "13") (name "Net-(LED6-DO)") (class "Default")
      (node (ref "LED6") (pin "2-DOUT") (pinfunction "DO_2-DOUT") (pintype "output"))
      (node (ref "LED7") (pin "4-DIN") (pinfunction "DI_4-DIN") (pintype "input"))
    )
    (net (code "14") (name "Net-(LED7-DO)") (class "Default")
      (node (ref "LED7") (pin "2-DOUT") (pinfunction "DO_2-DOUT") (pintype "output"))
      (node (ref "LED8") (pin "4-DIN") (pinfunction "DI_4-DIN") (pintype "input"))
    )
    (net (code "15") (name "Net-(LED8-DO)") (class "Default")
      (node (ref "LED8") (pin "2-DOUT") (pinfunction "DO_2-DOUT") (pintype "output"))
      (node (ref "LED9") (pin "4-DIN") (pinfunction "DI_4-DIN") (pintype "input"))
    )
    (net (code "16") (name "Net-(LED10-DI)") (class "Default")
      (node (ref "LED10") (pin "4-DIN") (pinfunction "DI_4-DIN") (pintype "input"))
      (node (ref "LED9") (pin "2-DOUT") (pinfunction "DO_2-DOUT") (pintype "output"))
    )
    (net (code "17") (name "Net-(LED10-DO)") (class "Default")
      (node (ref "LED10") (pin "2-DOUT") (pinfunction "DO_2-DOUT") (pintype "output"))
      (node (ref "LED11") (pin "4-DIN") (pinfunction "DI_4-DIN") (pintype "input"))
    )
    (net (code "18") (name "Net-(LED11-DO)") (class "Default")
      (node (ref "LED11") (pin "2-DOUT") (pinfunction "DO_2-DOUT") (pintype "output"))
      (node (ref "LED12") (pin "4-DIN") (pinfunction "DI_4-DIN") (pintype "input"))
    )
    (net (code "19") (name "Net-(LED12-DO)") (class "Default")
      (node (ref "LED12") (pin "2-DOUT") (pinfunction "DO_2-DOUT") (pintype "output"))
      (node (ref "LED13") (pin "4-DIN") (pinfunction "DI_4-DIN") (pintype "input"))
    )
    (net (code "20") (name "Net-(LED13-DO)") (class "Default")
      (node (ref "LED13") (pin "2-DOUT") (pinfunction "DO_2-DOUT") (pintype "output"))
      (node (ref "LED14") (pin "4-DIN") (pinfunction "DI_4-DIN") (pintype "input"))
    )
    (net (code "21") (name "Net-(LED14-DO)") (class "Default")
      (node (ref "LED14") (pin "2-DOUT") (pinfunction "DO_2-DOUT") (pintype "output"))
      (node (ref "LED15") (pin "4-DIN") (pinfunction "DI_4-DIN") (pintype "input"))
    )
    (net (code "22") (name "Net-(LED15-DO)") (class "Default")
      (node (ref "LED15") (pin "2-DOUT") (pinfunction "DO_2-DOUT") (pintype "output"))
      (node (ref "LED16") (pin "4-DIN") (pinfunction "DI_4-DIN") (pintype "input"))
    )
    (net (code "23") (name "Net-(LED16-DO)") (class "Default")
      (node (ref "LED16") (pin "2-DOUT") (pinfunction "DO_2-DOUT") (pintype "output"))
      (node (ref "LED17") (pin "4-DIN") (pinfunction "DI_4-DIN") (pintype "input"))
    )
    (net (code "24") (name "Net-(LED17-DO)") (class "Default")
      (node (ref "LED17") (pin "2-DOUT") (pinfunction "DO_2-DOUT") (pintype "output"))
      (node (ref "LED18") (pin "4-DIN") (pinfunction "DI_4-DIN") (pintype "input"))
    )
    (net (code "25") (name "Net-(LED18-DO)") (class "Default")
      (node (ref "LED18") (pin "2-DOUT") (pinfunction "DO_2-DOUT") (pintype "output"))
      (node (ref "LED19") (pin "4-DIN") (pinfunction "DI_4-DIN") (pintype "input"))
    )
    (net (code "26") (name "Net-(LED19-DO)") (class "Default")
      (node (ref "LED19") (pin "2-DOUT") (pinfunction "DO_2-DOUT") (pintype "output"))
      (node (ref "LED20") (pin "4-DIN") (pinfunction "DI_4-DIN") (pintype "input"))
    )
    (net (code "27") (name "Net-(LED20-DO)") (class "Default")
      (node (ref "LED20") (pin "2-DOUT") (pinfunction "DO_2-DOUT") (pintype "output"))
      (node (ref "LED21") (pin "4-DIN") (pinfunction "DI_4-DIN") (pintype "input"))
    )
    (net (code "28") (name "Net-(LED21-DO)") (class "Default")
      (node (ref "LED21") (pin "2-DOUT") (pinfunction "DO_2-DOUT") (pintype "output"))
      (node (ref "LED22") (pin "4-DIN") (pinfunction "DI_4-DIN") (pintype "input"))
    )
    (net (code "29") (name "Net-(LED22-DO)") (class "Default")
      (node (ref "LED22") (pin "2-DOUT") (pinfunction "DO_2-DOUT") (pintype "output"))
      (node (ref "LED23") (pin "4-DIN") (pinfunction "DI_4-DIN") (pintype "input"))
    )
    (net (code "30") (name "Net-(LED23-DO)") (class "Default")
      (node (ref "LED23") (pin "2-DOUT") (pinfunction "DO_2-DOUT") (pintype "output"))
      (node (ref "LED24") (pin "4-DIN") (pinfunction "DI_4-DIN") (pintype "input"))
    )
    (net (code "31") (name "Net-(LED24-DO)") (class "Default")
      (node (ref "LED24") (pin "2-DOUT") (pinfunction "DO_2-DOUT") (pintype "output"))
      (node (ref "LED25") (pin "4-DIN") (pinfunction "DI_4-DIN") (pintype "input"))
    )
    (net (code "32") (name "Net-(LED25-DO)") (class "Default")
      (node (ref "LED25") (pin "2-DOUT") (pinfunction "DO_2-DOUT") (pintype "output"))
      (node (ref "LED26") (pin "4-DIN") (pinfunction "DI_4-DIN") (pintype "input"))
    )
    (net (code "33") (name "Net-(LED26-DO)") (class "Default")
      (node (ref "LED26") (pin "2-DOUT") (pinfunction "DO_2-DOUT") (pintype "output"))
      (node (ref "LED27") (pin "4-DIN") (pinfunction "DI_4-DIN") (pintype "input"))
    )
    (net (code "34") (name "Net-(LED27-DO)") (class "Default")
      (node (ref "LED27") (pin "2-DOUT") (pinfunction "DO_2-DOUT") (pintype "output"))
      (node (ref "LED28") (pin "4-DIN") (pinfunction "DI_4-DIN") (pintype "input"))
    )
    (net (code "35") (name "Net-(LED28-DO)") (class "Default")
      (node (ref "LED28") (pin "2-DOUT") (pinfunction "DO_2-DOUT") (pintype "output"))
      (node (ref "LED29") (pin "4-DIN") (pinfunction "DI_4-DIN") (pintype "input"))
    )
    (net (code "36") (name "Net-(LED29-DO)") (class "Default")
      (node (ref "LED29") (pin "2-DOUT") (pinfunction "DO_2-DOUT") (pintype "output"))
      (node (ref "LED30") (pin "4-DIN") (pinfunction "DI_4-DIN") (pintype "input"))
    )
    (net (code "37") (name "Net-(LED30-DO)") (class "Default")
      (node (ref "LED30") (pin "2-DOUT") (pinfunction "DO_2-DOUT") (pintype "output"))
      (node (ref "LED31") (pin "4-DIN") (pinfunction "DI_4-DIN") (pintype "input"))
    )
    (net (code "38") (name "Net-(LED31-DO)") (class "Default")
      (node (ref "LED31") (pin "2-DOUT") (pinfunction "DO_2-DOUT") (pintype "output"))
      (node (ref "LED32") (pin "4-DIN") (pinfunction "DI_4-DIN") (pintype "input"))
    )
    (net (code "39") (name "Net-(LED32-DO)") (class "Default")
      (node (ref "LED32") (pin "2-DOUT") (pinfunction "DO_2-DOUT") (pintype "output"))
      (node (ref "LED33") (pin "4-DIN") (pinfunction "DI_4-DIN") (pintype "input"))
    )
    (net (code "40") (name "Net-(LED33-DO)") (class "Default")
      (node (ref "LED33") (pin "2-DOUT") (pinfunction "DO_2-DOUT") (pintype "output"))
      (node (ref "LED34") (pin "4-DIN") (pinfunction "DI_4-DIN") (pintype "input"))
    )
    (net (code "41") (name "Net-(LED34-DO)") (class "Default")
      (node (ref "LED34") (pin "2-DOUT") (pinfunction "DO_2-DOUT") (pintype "output"))
      (node (ref "LED35") (pin "4-DIN") (pinfunction "DI_4-DIN") (pintype "input"))
    )
    (net (code "42") (name "Net-(LED35-DO)") (class "Default")
      (node (ref "LED35") (pin "2-DOUT") (pinfunction "DO_2-DOUT") (pintype "output"))
      (node (ref "LED36") (pin "4-DIN") (pinfunction "DI_4-DIN") (pintype "input"))
    )
    (net (code "43") (name "Net-(LED36-DO)") (class "Default")
      (node (ref "LED36") (pin "2-DOUT") (pinfunction "DO_2-DOUT") (pintype "output"))
      (node (ref "LED37") (pin "4-DIN") (pinfunction "DI_4-DIN") (pintype "input"))
    )
    (net (code "44") (name "Net-(LED37-DO)") (class "Default")
      (node (ref "LED37") (pin "2-DOUT") (pinfunction "DO_2-DOUT") (pintype "output"))
      (node (ref "LED38") (pin "4-DIN") (pinfunction "DI_4-DIN") (pintype "input"))
    )
    (net (code "45") (name "Net-(LED38-DO)") (class "Default")
      (node (ref "LED38") (pin "2-DOUT") (pinfunction "DO_2-DOUT") (pintype "output"))
      (node (ref "LED39") (pin "4-DIN") (pinfunction "DI_4-DIN") (pintype "input"))
    )
    (net (code "46") (name "Net-(LED39-DO)") (class "Default")
      (node (ref "LED39") (pin "2-DOUT") (pinfunction "DO_2-DOUT") (pintype "output"))
      (node (ref "LED40") (pin "4-DIN") (pinfunction "DI_4-DIN") (pintype "input"))
    )
    (net (code "47") (name "Net-(LED40-DO)") (class "Default")
      (node (ref "LED40") (pin "2-DOUT") (pinfunction "DO_2-DOUT") (pintype "output"))
      (node (ref "LED41") (pin "4-DIN") (pinfunction "DI_4-DIN") (pintype "input"))
    )
    (net (code "48") (name "Net-(LED41-DO)") (class "Default")
      (node (ref "LED41") (pin "2-DOUT") (pinfunction "DO_2-DOUT") (pintype "output"))
      (node (ref "LED42") (pin "4-DIN") (pinfunction "DI_4-DIN") (pintype "input"))
    )
    (net (code "49") (name "Net-(LED42-DO)") (class "Default")
      (node (ref "LED42") (pin "2-DOUT") (pinfunction "DO_2-DOUT") (pintype "output"))
      (node (ref "LED43") (pin "4-DIN") (pinfunction "DI_4-DIN") (pintype "input"))
    )
    (net (code "50") (name "Net-(LED43-DO)") (class "Default")
      (node (ref "LED43") (pin "2-DOUT") (pinfunction "DO_2-DOUT") (pintype "output"))
      (node (ref "LED44") (pin "4-DIN") (pinfunction "DI_4-DIN") (pintype "input"))
    )
    (net (code "51") (name "Net-(LED44-DO)") (class "Default")
      (node (ref "LED44") (pin "2-DOUT") (pinfunction "DO_2-DOUT") (pintype "output"))
      (node (ref "LED45") (pin "4-DIN") (pinfunction "DI_4-DIN") (pintype "input"))
    )
    (net (code "52") (name "Net-(LED45-DO)") (class "Default")
      (node (ref "LED45") (pin "2-DOUT") (pinfunction "DO_2-DOUT") (pintype "output"))
      (node (ref "LED46") (pin "4-DIN") (pinfunction "DI_4-DIN") (pintype "input"))
    )
    (net (code "53") (name "Net-(LED46-DO)") (class "Default")
      (node (ref "LED46") (pin "2-DOUT") (pinfunction "DO_2-DOUT") (pintype "output"))
      (node (ref "LED47") (pin "4-DIN") (pinfunction "DI_4-DIN") (pintype "input"))
    )
    (net (code "54") (name "Net-(LED47-DO)") (class "Default")
      (node (ref "LED47") (pin "2-DOUT") (pinfunction "DO_2-DOUT") (pintype "output"))
      (node (ref "LED48") (pin "4-DIN") (pinfunction "DI_4-DIN") (pintype "input"))
    )
    (net (code "55") (name "Net-(LED48-DO)") (class "Default")
      (node (ref "LED48") (pin "2-DOUT") (pinfunction "DO_2-DOUT") (pintype "output"))
      (node (ref "LED49") (pin "4-DIN") (pinfunction "DI_4-DIN") (pintype "input"))
    )
    (net (code "56") (name "Net-(LED49-DO)") (class "Default")
      (node (ref "LED49") (pin "2-DOUT") (pinfunction "DO_2-DOUT") (pintype "output"))
      (node (ref "LED50") (pin "4-DIN") (pinfunction "DI_4-DIN") (pintype "input"))
    )
    (net (code "57") (name "Net-(LED50-DO)") (class "Default")
      (node (ref "LED50") (pin "2-DOUT") (pinfunction "DO_2-DOUT") (pintype "output"))
      (node (ref "LED51") (pin "4-DIN") (pinfunction "DI_4-DIN") (pintype "input"))
    )
    (net (code "58") (name "Net-(LED51-DO)") (class "Default")
      (node (ref "LED51") (pin "2-DOUT") (pinfunction "DO_2-DOUT") (pintype "output"))
      (node (ref "LED52") (pin "4-DIN") (pinfunction "DI_4-DIN") (pintype "input"))
    )
    (net (code "59") (name "Net-(LED52-DO)") (class "Default")
      (node (ref "LED52") (pin "2-DOUT") (pinfunction "DO_2-DOUT") (pintype "output"))
      (node (ref "LED53") (pin "4-DIN") (pinfunction "DI_4-DIN") (pintype "input"))
    )
    (net (code "60") (name "Net-(LED53-DO)") (class "Default")
      (node (ref "LED53") (pin "2-DOUT") (pinfunction "DO_2-DOUT") (pintype "output"))
      (node (ref "LED54") (pin "4-DIN") (pinfunction "DI_4-DIN") (pintype "input"))
    )
    (net (code "61") (name "Net-(LED54-DO)") (class "Default")
      (node (ref "LED54") (pin "2-DOUT") (pinfunction "DO_2-DOUT") (pintype "output"))
      (node (ref "LED55") (pin "4-DIN") (pinfunction "DI_4-DIN") (pintype "input"))
    )
    (net (code "62") (name "Net-(LED55-DO)") (class "Default")
      (node (ref "LED55") (pin "2-DOUT") (pinfunction "DO_2-DOUT") (pintype "output"))
      (node (ref "LED56") (pin "4-DIN") (pinfunction "DI_4-DIN") (pintype "input"))
    )
    (net (code "63") (name "Net-(LED56-DO)") (class "Default")
      (node (ref "LED56") (pin "2-DOUT") (pinfunction "DO_2-DOUT") (pintype "output"))
      (node (ref "LED57") (pin "4-DIN") (pinfunction "DI_4-DIN") (pintype "input"))
    )
    (net (code "64") (name "Net-(LED57-DO)") (class "Default")
      (node (ref "LED57") (pin "2-DOUT") (pinfunction "DO_2-DOUT") (pintype "output"))
      (node (ref "LED58") (pin "4-DIN") (pinfunction "DI_4-DIN") (pintype "input"))
    )
    (net (code "65") (name "Net-(LED58-DO)") (class "Default")
      (node (ref "LED58") (pin "2-DOUT") (pinfunction "DO_2-DOUT") (pintype "output"))
      (node (ref "LED59") (pin "4-DIN") (pinfunction "DI_4-DIN") (pintype "input"))
    )
    (net (code "66") (name "Net-(LED59-DO)") (class "Default")
      (node (ref "LED59") (pin "2-DOUT") (pinfunction "DO_2-DOUT") (pintype "output"))
      (node (ref "LED60") (pin "4-DIN") (pinfunction "DI_4-DIN") (pintype "input"))
    )
    (net (code "67") (name "Net-(LED60-DO)") (class "Default")
      (node (ref "LED60") (pin "2-DOUT") (pinfunction "DO_2-DOUT") (pintype "output"))
      (node (ref "LED61") (pin "4-DIN") (pinfunction "DI_4-DIN") (pintype "input"))
    )
    (net (code "68") (name "Net-(LED61-DO)") (class "Default")
      (node (ref "LED61") (pin "2-DOUT") (pinfunction "DO_2-DOUT") (pintype "output"))
      (node (ref "LED62") (pin "4-DIN") (pinfunction "DI_4-DIN") (pintype "input"))
    )
    (net (code "69") (name "Net-(LED62-DO)") (class "Default")
      (node (ref "LED62") (pin "2-DOUT") (pinfunction "DO_2-DOUT") (pintype "output"))
      (node (ref "LED63") (pin "4-DIN") (pinfunction "DI_4-DIN") (pintype "input"))
    )
    (net (code "70") (name "Net-(LED63-DO)") (class "Default")
      (node (ref "LED63") (pin "2-DOUT") (pinfunction "DO_2-DOUT") (pintype "output"))
      (node (ref "LED64") (pin "4-DIN") (pinfunction "DI_4-DIN") (pintype "input"))
    )
    (net (code "71") (name "Net-(LED64-DO)") (class "Default")
      (node (ref "LED64") (pin "2-DOUT") (pinfunction "DO_2-DOUT") (pintype "output"))
      (node (ref "LED65") (pin "4-DIN") (pinfunction "DI_4-DIN") (pintype "input"))
    )
    (net (code "72") (name "Net-(LED65-DO)") (class "Default")
      (node (ref "LED65") (pin "2-DOUT") (pinfunction "DO_2-DOUT") (pintype "output"))
      (node (ref "LED66") (pin "4-DIN") (pinfunction "DI_4-DIN") (pintype "input"))
    )
    (net (code "73") (name "Net-(LED66-DO)") (class "Default")
      (node (ref "LED66") (pin "2-DOUT") (pinfunction "DO_2-DOUT") (pintype "output"))
      (node (ref "LED67") (pin "4-DIN") (pinfunction "DI_4-DIN") (pintype "input"))
    )
    (net (code "74") (name "Net-(LED67-DO)") (class "Default")
      (node (ref "LED67") (pin "2-DOUT") (pinfunction "DO_2-DOUT") (pintype "output"))
      (node (ref "LED68") (pin "4-DIN") (pinfunction "DI_4-DIN") (pintype "input"))
    )
    (net (code "75") (name "Net-(LED68-DO)") (class "Default")
      (node (ref "LED68") (pin "2-DOUT") (pinfunction "DO_2-DOUT") (pintype "output"))
      (node (ref "LED69") (pin "4-DIN") (pinfunction "DI_4-DIN") (pintype "input"))
    )
    (net (code "76") (name "Net-(LED69-DO)") (class "Default")
      (node (ref "LED69") (pin "2-DOUT") (pinfunction "DO_2-DOUT") (pintype "output"))
      (node (ref "LED70") (pin "4-DIN") (pinfunction "DI_4-DIN") (pintype "input"))
    )
    (net (code "77") (name "Net-(LED70-DO)") (class "Default")
      (node (ref "LED70") (pin "2-DOUT") (pinfunction "DO_2-DOUT") (pintype "output"))
      (node (ref "LED71") (pin "4-DIN") (pinfunction "DI_4-DIN") (pintype "input"))
    )
    (net (code "78") (name "Net-(LED71-DO)") (class "Default")
      (node (ref "LED71") (pin "2-DOUT") (pinfunction "DO_2-DOUT") (pintype "output"))
      (node (ref "LED72") (pin "4-DIN") (pinfunction "DI_4-DIN") (pintype "input"))
    )
    (net (code "79") (name "Net-(LED72-DO)") (class "Default")
      (node (ref "LED72") (pin "2-DOUT") (pinfunction "DO_2-DOUT") (pintype "output"))
      (node (ref "LED73") (pin "4-DIN") (pinfunction "DI_4-DIN") (pintype "input"))
    )
    (net (code "80") (name "Net-(LED73-DO)") (class "Default")
      (node (ref "LED73") (pin "2-DOUT") (pinfunction "DO_2-DOUT") (pintype "output"))
      (node (ref "LED74") (pin "4-DIN") (pinfunction "DI_4-DIN") (pintype "input"))
    )
    (net (code "81") (name "Net-(LED74-DO)") (class "Default")
      (node (ref "LED74") (pin "2-DOUT") (pinfunction "DO_2-DOUT") (pintype "output"))
      (node (ref "LED75") (pin "4-DIN") (pinfunction "DI_4-DIN") (pintype "input"))
    )
    (net (code "82") (name "Net-(LED75-DO)") (class "Default")
      (node (ref "LED75") (pin "2-DOUT") (pinfunction "DO_2-DOUT") (pintype "output"))
      (node (ref "LED76") (pin "4-DIN") (pinfunction "DI_4-DIN") (pintype "input"))
    )
    (net (code "83") (name "Net-(LED76-DO)") (class "Default")
      (node (ref "LED76") (pin "2-DOUT") (pinfunction "DO_2-DOUT") (pintype "output"))
      (node (ref "LED77") (pin "4-DIN") (pinfunction "DI_4-DIN") (pintype "input"))
    )
    (net (code "84") (name "Net-(LED77-DO)") (class "Default")
      (node (ref "LED77") (pin "2-DOUT") (pinfunction "DO_2-DOUT") (pintype "output"))
      (node (ref "LED78") (pin "4-DIN") (pinfunction "DI_4-DIN") (pintype "input"))
    )
    (net (code "85") (name "Net-(LED78-DO)") (class "Default")
      (node (ref "LED78") (pin "2-DOUT") (pinfunction "DO_2-DOUT") (pintype "output"))
      (node (ref "LED79") (pin "4-DIN") (pinfunction "DI_4-DIN") (pintype "input"))
    )
    (net (code "86") (name "Net-(LED79-DO)") (class "Default")
      (node (ref "LED79") (pin "2-DOUT") (pinfunction "DO_2-DOUT") (pintype "output"))
      (node (ref "LED80") (pin "4-DIN") (pinfunction "DI_4-DIN") (pintype "input"))
    )
    (net (code "87") (name "Net-(LED80-DO)") (class "Default")
      (node (ref "LED80") (pin "2-DOUT") (pinfunction "DO_2-DOUT") (pintype "output"))
      (node (ref "LED81") (pin "4-DIN") (pinfunction "DI_4-DIN") (pintype "input"))
    )
    (net (code "88") (name "Net-(LED81-DO)") (class "Default")
      (node (ref "LED81") (pin "2-DOUT") (pinfunction "DO_2-DOUT") (pintype "output"))
      (node (ref "LED82") (pin "4-DIN") (pinfunction "DI_4-DIN") (pintype "input"))
    )
    (net (code "89") (name "Net-(LED82-DO)") (class "Default")
      (node (ref "LED82") (pin "2-DOUT") (pinfunction "DO_2-DOUT") (pintype "output"))
      (node (ref "LED83") (pin "4-DIN") (pinfunction "DI_4-DIN") (pintype "input"))
    )
    (net (code "90") (name "Net-(LED83-DO)") (class "Default")
      (node (ref "LED83") (pin "2-DOUT") (pinfunction "DO_2-DOUT") (pintype "output"))
      (node (ref "LED84") (pin "4-DIN") (pinfunction "DI_4-DIN") (pintype "input"))
    )
    (net (code "91") (name "Net-(LED84-DO)") (class "Default")
      (node (ref "LED84") (pin "2-DOUT") (pinfunction "DO_2-DOUT") (pintype "output"))
      (node (ref "LED85") (pin "4-DIN") (pinfunction "DI_4-DIN") (pintype "input"))
    )
    (net (code "92") (name "Net-(LED85-DO)") (class "Default")
      (node (ref "LED85") (pin "2-DOUT") (pinfunction "DO_2-DOUT") (pintype "output"))
      (node (ref "LED86") (pin "4-DIN") (pinfunction "DI_4-DIN") (pintype "input"))
    )
    (net (code "93") (name "Net-(LED86-DO)") (class "Default")
      (node (ref "LED86") (pin "2-DOUT") (pinfunction "DO_2-DOUT") (pintype "output"))
      (node (ref "LED87") (pin "4-DIN") (pinfunction "DI_4-DIN") (pintype "input"))
    )
    (net (code "94") (name "Net-(LED87-DO)") (class "Default")
      (node (ref "LED87") (pin "2-DOUT") (pinfunction "DO_2-DOUT") (pintype "output"))
      (node (ref "LED88") (pin "4-DIN") (pinfunction "DI_4-DIN") (pintype "input"))
    )
    (net (code "95") (name "Net-(LED88-DO)") (class "Default")
      (node (ref "LED88") (pin "2-DOUT") (pinfunction "DO_2-DOUT") (pintype "output"))
      (node (ref "LED89") (pin "4-DIN") (pinfunction "DI_4-DIN") (pintype "input"))
    )
    (net (code "96") (name "Net-(LED89-DO)") (class "Default")
      (node (ref "LED89") (pin "2-DOUT") (pinfunction "DO_2-DOUT") (pintype "output"))
      (node (ref "LED90") (pin "4-DIN") (pinfunction "DI_4-DIN") (pintype "input"))
    )
    (net (code "97") (name "Net-(LED90-DO)") (class "Default")
      (node (ref "LED90") (pin "2-DOUT") (pinfunction "DO_2-DOUT") (pintype "output"))
      (node (ref "LED91") (pin "4-DIN") (pinfunction "DI_4-DIN") (pintype "input"))
    )
    (net (code "98") (name "Net-(LED91-DO)") (class "Default")
      (node (ref "LED91") (pin "2-DOUT") (pinfunction "DO_2-DOUT") (pintype "output"))
      (node (ref "LED92") (pin "4-DIN") (pinfunction "DI_4-DIN") (pintype "input"))
    )
    (net (code "99") (name "Net-(LED92-DO)") (class "Default")
      (node (ref "LED92") (pin "2-DOUT") (pinfunction "DO_2-DOUT") (pintype "output"))
      (node (ref "LED93") (pin "4-DIN") (pinfunction "DI_4-DIN") (pintype "input"))
    )
    (net (code "100") (name "Net-(LED93-DO)") (class "Default")
      (node (ref "LED93") (pin "2-DOUT") (pinfunction "DO_2-DOUT") (pintype "output"))
      (node (ref "LED94") (pin "4-DIN") (pinfunction "DI_4-DIN") (pintype "input"))
    )
    (net (code "101") (name "Net-(LED94-DO)") (class "Default")
      (node (ref "LED94") (pin "2-DOUT") (pinfunction "DO_2-DOUT") (pintype "output"))
      (node (ref "LED95") (pin "4-DIN") (pinfunction "DI_4-DIN") (pintype "input"))
    )
    (net (code "102") (name "Net-(LED95-DO)") (class "Default")
      (node (ref "LED95") (pin "2-DOUT") (pinfunction "DO_2-DOUT") (pintype "output"))
      (node (ref "LED96") (pin "4-DIN") (pinfunction "DI_4-DIN") (pintype "input"))
    )
    (net (code "103") (name "Net-(LEDPW-PadA)") (class "Default")
      (node (ref "LEDPW") (pin "A") (pinfunction "A_A") (pintype "passive"))
      (node (ref "R5") (pin "1") (pinfunction "1_1") (pintype "passive"))
    )
    (net (code "104") (name "Net-(LEDRX-PadC)") (class "Default")
      (node (ref "LEDRX") (pin "C") (pinfunction "C_C") (pintype "passive"))
      (node (ref "R4") (pin "2") (pinfunction "2_2") (pintype "passive"))
    )
    (net (code "105") (name "Net-(LEDTX-PadC)") (class "Default")
      (node (ref "LEDTX") (pin "C") (pinfunction "C_C") (pintype "passive"))
      (node (ref "R3") (pin "2") (pinfunction "2_2") (pintype "passive"))
    )
    (net (code "106") (name "Net-(U2-3V3OUT)") (class "Default")
      (node (ref "C1") (pin "1") (pinfunction "1_1") (pintype "passive"))
      (node (ref "C3") (pin "2") (pinfunction "2_2") (pintype "passive"))
      (node (ref "R2") (pin "2") (pinfunction "2_2") (pintype "passive"))
      (node (ref "U1") (pin "VCC") (pinfunction "VCC_VCC") (pintype "bidirectional"))
      (node (ref "U2") (pin "17") (pinfunction "3V3OUT_17") (pintype "power_in"))
      (node (ref "U3") (pin "2") (pinfunction "VCCA_2") (pintype "bidirectional"))
    )
    (net (code "107") (name "Net-(U2-AGND)") (class "Default")
      (node (ref "U2") (pin "18") (pinfunction "GND2_18") (pintype "power_in"))
      (node (ref "U2") (pin "21") (pinfunction "GND3_21") (pintype "power_in"))
      (node (ref "U2") (pin "25") (pinfunction "AGND_25") (pintype "power_in"))
      (node (ref "U2") (pin "7") (pinfunction "GND1_7") (pintype "power_in"))
    )
    (net (code "108") (name "Net-(U2-DTR)") (class "Default")
      (node (ref "C4") (pin "2") (pinfunction "2_2") (pintype "passive"))
      (node (ref "U2") (pin "2") (pinfunction "DTR_2") (pintype "bidirectional"))
    )
    (net (code "109") (name "Net-(U2-RXLED)") (class "Default")
      (node (ref "R4") (pin "1") (pinfunction "1_1") (pintype "passive"))
      (node (ref "U2") (pin "22") (pinfunction "RXLED_22") (pintype "bidirectional"))
    )
    (net (code "110") (name "Net-(U2-TXLED)") (class "Default")
      (node (ref "R3") (pin "1") (pinfunction "1_1") (pintype "passive"))
      (node (ref "U2") (pin "23") (pinfunction "TXLED_23") (pintype "bidirectional"))
    )
    (net (code "111") (name "Net-(U2-USB+)") (class "Default")
      (node (ref "CN1") (pin "D+") (pinfunction "D+_D+") (pintype "bidirectional"))
      (node (ref "U2") (pin "15") (pinfunction "USB+_15") (pintype "bidirectional"))
    )
    (net (code "112") (name "Net-(U2-USB-)") (class "Default")
      (node (ref "CN1") (pin "D-") (pinfunction "D-_D-") (pintype "bidirectional"))
      (node (ref "U2") (pin "16") (pinfunction "USB-_16") (pintype "bidirectional"))
    )
    (net (code "113") (name "Net-(U3-A1)") (class "Default")
      (node (ref "U1") (pin "GPIO12") (pinfunction "GPIO12_GPIO12") (pintype "bidirectional"))
      (node (ref "U3") (pin "1") (pinfunction "A1_1") (pintype "bidirectional"))
    )
    (net (code "114") (name "Net-(U3-B1)") (class "Default")
      (node (ref "R1") (pin "2") (pinfunction "2_2") (pintype "passive"))
      (node (ref "U3") (pin "20") (pinfunction "B1_20") (pintype "bidirectional"))
    )
    (net (code "115") (name "Net-(U3-OE)") (class "Default")
      (node (ref "R2") (pin "1") (pinfunction "1_1") (pintype "passive"))
      (node (ref "U3") (pin "10") (pinfunction "OE_10") (pintype "bidirectional"))
    )
    (net (code "116") (name "RST") (class "Default")
      (node (ref "C4") (pin "1") (pinfunction "1_1") (pintype "passive"))
      (node (ref "U1") (pin "RESET") (pinfunction "RESET_RESET") (pintype "bidirectional"))
    )
    (net (code "117") (name "RX") (class "Default")
      (node (ref "U1") (pin "RX") (pinfunction "RX_RX") (pintype "bidirectional"))
      (node (ref "U2") (pin "1") (pinfunction "TXD_1") (pintype "output"))
    )
    (net (code "118") (name "TX") (class "Default")
      (node (ref "U1") (pin "TX") (pinfunction "TX_TX") (pintype "bidirectional"))
      (node (ref "U2") (pin "5") (pinfunction "RXD_5") (pintype "input"))
    )
    (net (code "119") (name "unconnected-(CN1-PadID)") (class "Default")
      (node (ref "CN1") (pin "ID") (pinfunction "ID_ID") (pintype "bidirectional"))
    )
    (net (code "120") (name "unconnected-(LED96-DO-Pad2-DOUT)") (class "Default")
      (node (ref "LED96") (pin "2-DOUT") (pinfunction "DO_2-DOUT") (pintype "output"))
    )
    (net (code "121") (name "unconnected-(U1-PadADC)") (class "Default")
      (node (ref "U1") (pin "ADC") (pinfunction "ADC_ADC") (pintype "bidirectional"))
    )
    (net (code "122") (name "unconnected-(U1-PadCH_PD)") (class "Default")
      (node (ref "U1") (pin "CH_PD") (pinfunction "CH_PD_CH_PD") (pintype "bidirectional"))
    )
    (net (code "123") (name "unconnected-(U1-PadGPIO0)") (class "Default")
      (node (ref "U1") (pin "GPIO0") (pinfunction "GPIO0_GPIO0") (pintype "bidirectional"))
    )
    (net (code "124") (name "unconnected-(U1-PadGPIO2)") (class "Default")
      (node (ref "U1") (pin "GPIO2") (pinfunction "GPIO2_GPIO2") (pintype "bidirectional"))
    )
    (net (code "125") (name "unconnected-(U1-PadGPIO4)") (class "Default")
      (node (ref "U1") (pin "GPIO4") (pinfunction "GPIO4_GPIO4") (pintype "bidirectional"))
    )
    (net (code "126") (name "unconnected-(U1-PadGPIO5)") (class "Default")
      (node (ref "U1") (pin "GPIO5") (pinfunction "GPIO5_GPIO5") (pintype "bidirectional"))
    )
    (net (code "127") (name "unconnected-(U1-PadGPIO13)") (class "Default")
      (node (ref "U1") (pin "GPIO13") (pinfunction "GPIO13_GPIO13") (pintype "bidirectional"))
    )
    (net (code "128") (name "unconnected-(U1-PadGPIO14)") (class "Default")
      (node (ref "U1") (pin "GPIO14") (pinfunction "GPIO14_GPIO14") (pintype "bidirectional"))
    )
    (net (code "129") (name "unconnected-(U1-PadGPIO15)") (class "Default")
      (node (ref "U1") (pin "GPIO15") (pinfunction "GPIO15_GPIO15") (pintype "bidirectional"))
    )
    (net (code "130") (name "unconnected-(U1-PadGPIO16)") (class "Default")
      (node (ref "U1") (pin "GPIO16") (pinfunction "GPIO16_GPIO16") (pintype "bidirectional"))
    )
    (net (code "131") (name "unconnected-(U2-CTS-Pad11)") (class "Default")
      (node (ref "U2") (pin "11") (pinfunction "CTS_11") (pintype "bidirectional"))
    )
    (net (code "132") (name "unconnected-(U2-RTS-Pad3)") (class "Default")
      (node (ref "U2") (pin "3") (pinfunction "RTS_3") (pintype "bidirectional"))
    )
    (net (code "133") (name "unconnected-(U2-TEST-Pad26)") (class "Default")
      (node (ref "U2") (pin "26") (pinfunction "TEST_26") (pintype "input"))
    )
    (net (code "134") (name "unconnected-(U3-A2-Pad3)") (class "Default")
      (node (ref "U3") (pin "3") (pinfunction "A2_3") (pintype "bidirectional"))
    )
    (net (code "135") (name "unconnected-(U3-A3-Pad4)") (class "Default")
      (node (ref "U3") (pin "4") (pinfunction "A3_4") (pintype "bidirectional"))
    )
    (net (code "136") (name "unconnected-(U3-A4-Pad5)") (class "Default")
      (node (ref "U3") (pin "5") (pinfunction "A4_5") (pintype "bidirectional"))
    )
    (net (code "137") (name "unconnected-(U3-A5-Pad6)") (class "Default")
      (node (ref "U3") (pin "6") (pinfunction "A5_6") (pintype "bidirectional"))
    )
    (net (code "138") (name "unconnected-(U3-A6-Pad7)") (class "Default")
      (node (ref "U3") (pin "7") (pinfunction "A6_7") (pintype "bidirectional"))
    )
    (net (code "139") (name "unconnected-(U3-A7-Pad8)") (class "Default")
      (node (ref "U3") (pin "8") (pinfunction "A7_8") (pintype "bidirectional"))
    )
    (net (code "140") (name "unconnected-(U3-A8-Pad9)") (class "Default")
      (node (ref "U3") (pin "9") (pinfunction "A8_9") (pintype "bidirectional"))
    )
    (net (code "141") (name "unconnected-(U3-B2-Pad18)") (class "Default")
      (node (ref "U3") (pin "18") (pinfunction "B2_18") (pintype "bidirectional"))
    )
    (net (code "142") (name "unconnected-(U3-B3-Pad17)") (class "Default")
      (node (ref "U3") (pin "17") (pinfunction "B3_17") (pintype "bidirectional"))
    )
    (net (code "143") (name "unconnected-(U3-B4-Pad16)") (class "Default")
      (node (ref "U3") (pin "16") (pinfunction "B4_16") (pintype "bidirectional"))
    )
    (net (code "144") (name "unconnected-(U3-B5-Pad15)") (class "Default")
      (node (ref "U3") (pin "15") (pinfunction "B5_15") (pintype "bidirectional"))
    )
    (net (code "145") (name "unconnected-(U3-B6-Pad14)") (class "Default")
      (node (ref "U3") (pin "14") (pinfunction "B6_14") (pintype "bidirectional"))
    )
    (net (code "146") (name "unconnected-(U3-B7-Pad13)") (class "Default")
      (node (ref "U3") (pin "13") (pinfunction "B7_13") (pintype "bidirectional"))
    )
    (net (code "147") (name "unconnected-(U3-B8-Pad12)") (class "Default")
      (node (ref "U3") (pin "12") (pinfunction "B8_12") (pintype "bidirectional"))
    )
  )
)
